# core_io4.net
KiCad netlist of a schematic drawn in EAGLE
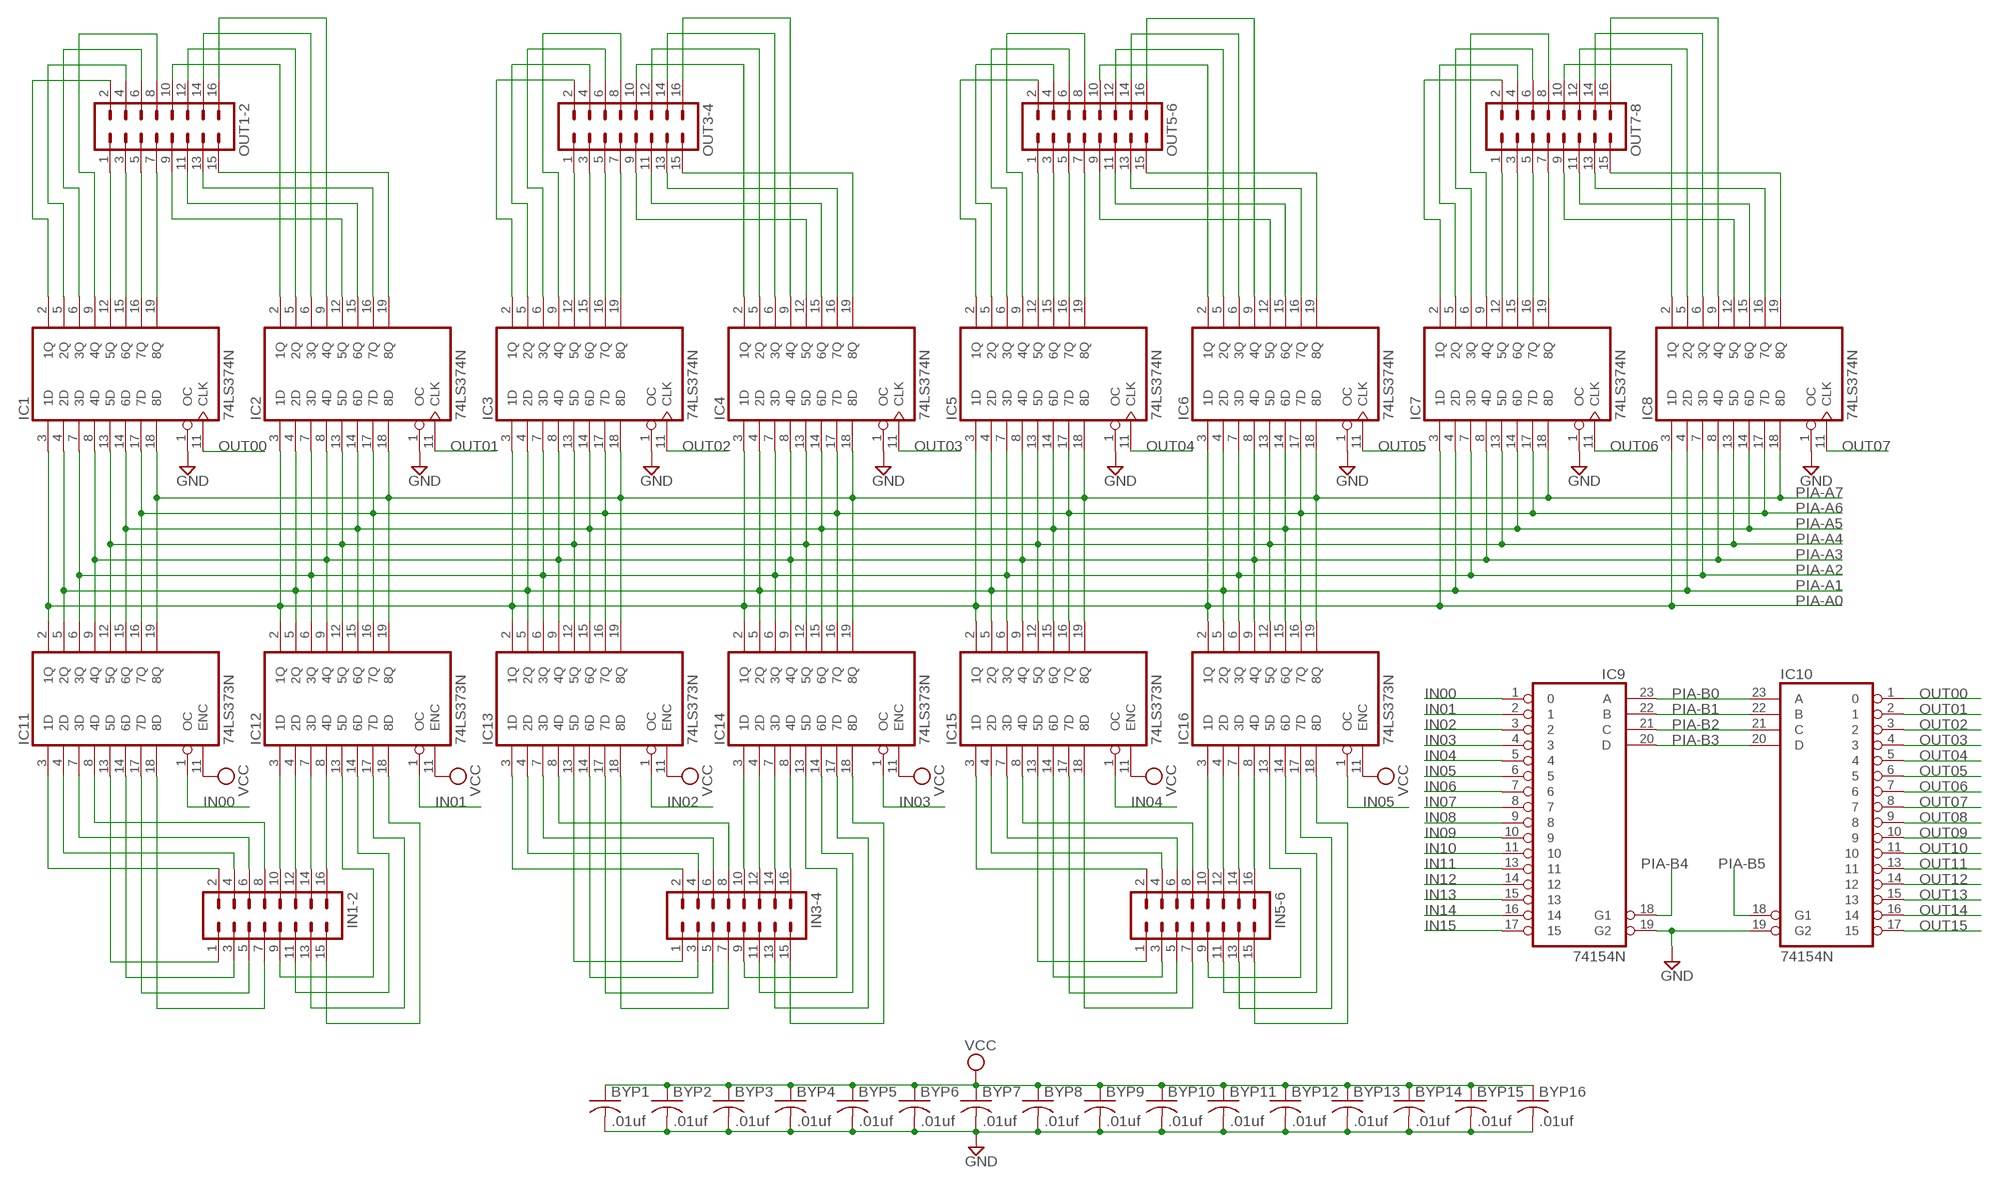
[diagram p0: schematic, sheet 1]
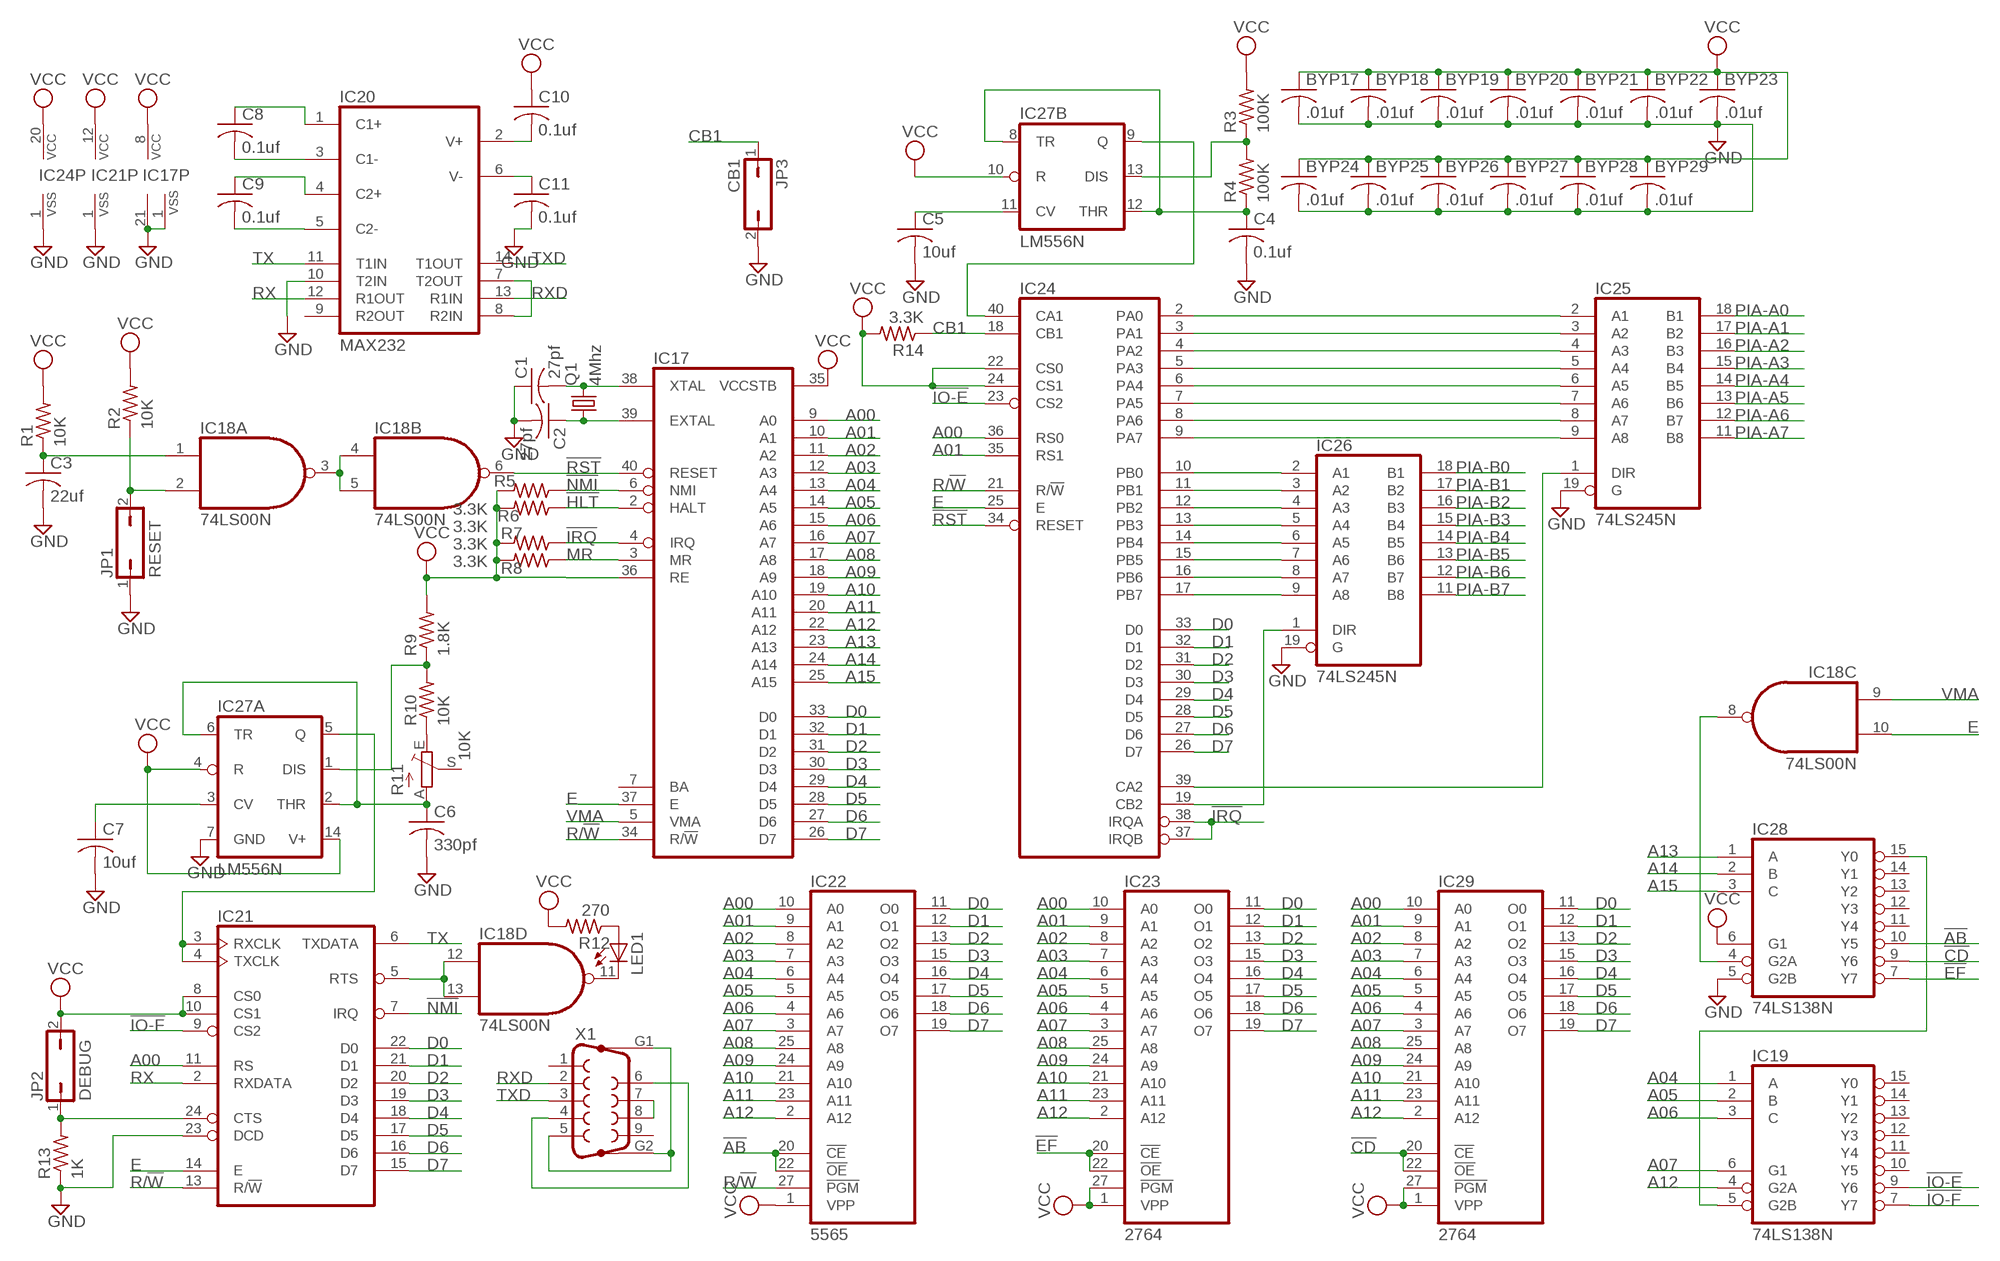
[diagram p1: schematic, sheet 2]
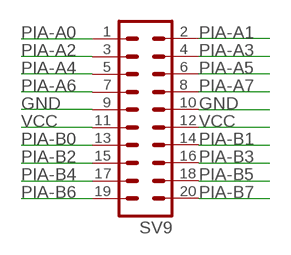
[diagram p2: schematic, sheet 3]

(export (version "E")
  (design (tool "Eeschema 10.0.6"))
  (components
    (comp (ref "BYP17")
      (value ".01uf")
      (footprint "eagle-import:C050-025X075")
      (libsource (lib "eagle-import") (part "C-US050-025X075"))
    )
    (comp (ref "BYP18")
      (value ".01uf")
      (footprint "eagle-import:C050-025X075")
      (libsource (lib "eagle-import") (part "C-US050-025X075"))
    )
    (comp (ref "BYP19")
      (value ".01uf")
      (footprint "eagle-import:C050-025X075")
      (libsource (lib "eagle-import") (part "C-US050-025X075"))
    )
    (comp (ref "BYP20")
      (value ".01uf")
      (footprint "eagle-import:C050-025X075")
      (libsource (lib "eagle-import") (part "C-US050-025X075"))
    )
    (comp (ref "BYP21")
      (value ".01uf")
      (footprint "eagle-import:C050-025X075")
      (libsource (lib "eagle-import") (part "C-US050-025X075"))
    )
    (comp (ref "BYP22")
      (value ".01uf")
      (footprint "eagle-import:C050-025X075")
      (libsource (lib "eagle-import") (part "C-US050-025X075"))
    )
    (comp (ref "BYP23")
      (value ".01uf")
      (footprint "eagle-import:C050-025X075")
      (libsource (lib "eagle-import") (part "C-US050-025X075"))
    )
    (comp (ref "BYP24")
      (value ".01uf")
      (footprint "eagle-import:C050-025X075")
      (libsource (lib "eagle-import") (part "C-US050-025X075"))
    )
    (comp (ref "BYP25")
      (value ".01uf")
      (footprint "eagle-import:C050-025X075")
      (libsource (lib "eagle-import") (part "C-US050-025X075"))
    )
    (comp (ref "BYP26")
      (value ".01uf")
      (footprint "eagle-import:C050-025X075")
      (libsource (lib "eagle-import") (part "C-US050-025X075"))
    )
    (comp (ref "BYP27")
      (value ".01uf")
      (footprint "eagle-import:C050-025X075")
      (libsource (lib "eagle-import") (part "C-US050-025X075"))
    )
    (comp (ref "BYP28")
      (value ".01uf")
      (footprint "eagle-import:C050-025X075")
      (libsource (lib "eagle-import") (part "C-US050-025X075"))
    )
    (comp (ref "BYP29")
      (value ".01uf")
      (footprint "eagle-import:C050-025X075")
      (libsource (lib "eagle-import") (part "C-US050-025X075"))
    )
    (comp (ref "C1")
      (value "27pf")
      (footprint "eagle-import:C050-025X075")
      (libsource (lib "eagle-import") (part "C-US050-025X075"))
    )
    (comp (ref "C2")
      (value "27pf")
      (footprint "eagle-import:C050-025X075")
      (libsource (lib "eagle-import") (part "C-US050-025X075"))
    )
    (comp (ref "C3")
      (value "22uf")
      (footprint "eagle-import:C102-043X133")
      (libsource (lib "eagle-import") (part "C-US102-043X133"))
    )
    (comp (ref "C4")
      (value "0.1uf")
      (footprint "eagle-import:C050-025X075")
      (libsource (lib "eagle-import") (part "C-US050-025X075"))
    )
    (comp (ref "C5")
      (value "10uf")
      (footprint "eagle-import:C050-025X075")
      (libsource (lib "eagle-import") (part "C-US050-025X075"))
    )
    (comp (ref "C6")
      (value "330pf")
      (footprint "eagle-import:C050-025X075")
      (libsource (lib "eagle-import") (part "C-US050-025X075"))
    )
    (comp (ref "C7")
      (value "10uf")
      (footprint "eagle-import:C050-025X075")
      (libsource (lib "eagle-import") (part "C-US050-025X075"))
    )
    (comp (ref "C8")
      (value "0.1uf")
      (footprint "eagle-import:C050-025X075")
      (libsource (lib "eagle-import") (part "C-US050-025X075"))
    )
    (comp (ref "C9")
      (value "0.1uf")
      (footprint "eagle-import:C050-025X075")
      (libsource (lib "eagle-import") (part "C-US050-025X075"))
    )
    (comp (ref "C10")
      (value "0.1uf")
      (footprint "eagle-import:C050-025X075")
      (libsource (lib "eagle-import") (part "C-US050-025X075"))
    )
    (comp (ref "C11")
      (value "0.1uf")
      (footprint "eagle-import:C050-025X075")
      (libsource (lib "eagle-import") (part "C-US050-025X075"))
    )
    (comp (ref "IC17")
      (value "6802")
      (footprint "eagle-import:DIL40")
      (libsource (lib "eagle-import") (part "6802"))
    )
    (comp (ref "IC18")
      (value "74LS00N")
      (footprint "eagle-import:DIL14")
      (libsource (lib "eagle-import") (part "7400NLS"))
    )
    (comp (ref "IC19")
      (value "74LS138N")
      (footprint "eagle-import:DIL16")
      (libsource (lib "eagle-import") (part "74138NLS"))
    )
    (comp (ref "IC20")
      (value "MAX232")
      (footprint "eagle-import:DIL16")
      (fields (field (name "MF") "MAXIM") (field (name "MPN") "MAX232ACPE+"))
      (libsource (lib "eagle-import") (part "MAX232"))
    )
    (comp (ref "IC21")
      (value "6850")
      (footprint "eagle-import:DIL24")
      (fields (field (name "MF") "NTE ELECTRONICS") (field (name "MPN") "NTE6850"))
      (libsource (lib "eagle-import") (part "6850"))
    )
    (comp (ref "IC22")
      (value "5565")
      (footprint "eagle-import:DIL28")
      (libsource (lib "eagle-import") (part "2764"))
    )
    (comp (ref "IC23")
      (value "2764")
      (footprint "eagle-import:DIL28")
      (libsource (lib "eagle-import") (part "2764"))
    )
    (comp (ref "IC24")
      (value "6821")
      (footprint "eagle-import:DIL40")
      (fields (field (name "MF") "NTE ELECTRONICS") (field (name "MPN") "NTE6821"))
      (libsource (lib "eagle-import") (part "6821"))
    )
    (comp (ref "IC25")
      (value "74LS245N")
      (footprint "eagle-import:DIL20")
      (libsource (lib "eagle-import") (part "74245NLS"))
    )
    (comp (ref "IC26")
      (value "74LS245N")
      (footprint "eagle-import:DIL20")
      (libsource (lib "eagle-import") (part "74245NLS"))
    )
    (comp (ref "IC27")
      (value "LM556N")
      (footprint "eagle-import:DIL14")
      (libsource (lib "eagle-import") (part "556NLM"))
    )
    (comp (ref "IC28")
      (value "74LS138N")
      (footprint "eagle-import:DIL16")
      (libsource (lib "eagle-import") (part "74138NLS"))
    )
    (comp (ref "IC29")
      (value "2764")
      (footprint "eagle-import:DIL28")
      (libsource (lib "eagle-import") (part "2764"))
    )
    (comp (ref "JP1")
      (value "RESET")
      (footprint "eagle-import:JP1")
      (libsource (lib "eagle-import") (part "JP1Q"))
    )
    (comp (ref "JP2")
      (value "DEBUG")
      (footprint "eagle-import:JP1")
      (libsource (lib "eagle-import") (part "JP1Q"))
    )
    (comp (ref "JP3")
      (value "CB1")
      (footprint "eagle-import:JP1")
      (libsource (lib "eagle-import") (part "JP1Q"))
    )
    (comp (ref "LED1")
      (value "LED3MM")
      (footprint "eagle-import:LED3MM")
      (libsource (lib "eagle-import") (part "LED3MM"))
    )
    (comp (ref "Q1")
      (value "4Mhz")
      (footprint "eagle-import:HC18U-V")
      (libsource (lib "eagle-import") (part "CRYSTALHC18U-V"))
    )
    (comp (ref "R1")
      (value "10K")
      (footprint "eagle-import:0207_7")
      (libsource (lib "eagle-import") (part "R-US_0207/7"))
    )
    (comp (ref "R2")
      (value "10K")
      (footprint "eagle-import:0207_7")
      (libsource (lib "eagle-import") (part "R-US_0207/7"))
    )
    (comp (ref "R3")
      (value "100K")
      (footprint "eagle-import:0207_7")
      (libsource (lib "eagle-import") (part "R-US_0207/7"))
    )
    (comp (ref "R4")
      (value "100K")
      (footprint "eagle-import:0207_7")
      (libsource (lib "eagle-import") (part "R-US_0207/7"))
    )
    (comp (ref "R5")
      (value "3.3K")
      (footprint "eagle-import:0207_7")
      (libsource (lib "eagle-import") (part "R-US_0207/7"))
    )
    (comp (ref "R6")
      (value "3.3K")
      (footprint "eagle-import:0207_7")
      (libsource (lib "eagle-import") (part "R-US_0207/7"))
    )
    (comp (ref "R7")
      (value "3.3K")
      (footprint "eagle-import:0207_7")
      (libsource (lib "eagle-import") (part "R-US_0207/7"))
    )
    (comp (ref "R8")
      (value "3.3K")
      (footprint "eagle-import:0207_7")
      (libsource (lib "eagle-import") (part "R-US_0207/7"))
    )
    (comp (ref "R9")
      (value "1.8K")
      (footprint "eagle-import:0207_7")
      (libsource (lib "eagle-import") (part "R-US_0207/7"))
    )
    (comp (ref "R10")
      (value "10K")
      (footprint "eagle-import:0207_7")
      (libsource (lib "eagle-import") (part "R-US_0207/7"))
    )
    (comp (ref "R11")
      (value "10K")
      (footprint "eagle-import:SP19L")
      (libsource (lib "eagle-import") (part "TRIM_EU-B90P"))
    )
    (comp (ref "R12")
      (value "270")
      (footprint "eagle-import:0207_7")
      (libsource (lib "eagle-import") (part "R-US_0207/7"))
    )
    (comp (ref "R13")
      (value "1K")
      (footprint "eagle-import:0207_7")
      (libsource (lib "eagle-import") (part "R-US_0207/7"))
    )
    (comp (ref "R14")
      (value "3.3K")
      (footprint "eagle-import:0207_7")
      (libsource (lib "eagle-import") (part "R-US_0207/7"))
    )
    (comp (ref "X1")
      (value "F09HP")
      (footprint "eagle-import:F09HP")
      (libsource (lib "eagle-import") (part "F09HP"))
    )
    (comp (ref "SV9")
      (value "MA10-2")
      (footprint "eagle-import:MA10-2")
      (libsource (lib "eagle-import") (part "MA10-2"))
    )
    (comp (ref "BYP1")
      (value ".01uf")
      (footprint "eagle-import:C050-025X075")
      (libsource (lib "eagle-import") (part "C-US050-025X075"))
    )
    (comp (ref "BYP2")
      (value ".01uf")
      (footprint "eagle-import:C050-025X075")
      (libsource (lib "eagle-import") (part "C-US050-025X075"))
    )
    (comp (ref "BYP3")
      (value ".01uf")
      (footprint "eagle-import:C050-025X075")
      (libsource (lib "eagle-import") (part "C-US050-025X075"))
    )
    (comp (ref "BYP4")
      (value ".01uf")
      (footprint "eagle-import:C050-025X075")
      (libsource (lib "eagle-import") (part "C-US050-025X075"))
    )
    (comp (ref "BYP5")
      (value ".01uf")
      (footprint "eagle-import:C050-025X075")
      (libsource (lib "eagle-import") (part "C-US050-025X075"))
    )
    (comp (ref "BYP6")
      (value ".01uf")
      (footprint "eagle-import:C050-025X075")
      (libsource (lib "eagle-import") (part "C-US050-025X075"))
    )
    (comp (ref "BYP7")
      (value ".01uf")
      (footprint "eagle-import:C050-025X075")
      (libsource (lib "eagle-import") (part "C-US050-025X075"))
    )
    (comp (ref "BYP8")
      (value ".01uf")
      (footprint "eagle-import:C050-025X075")
      (libsource (lib "eagle-import") (part "C-US050-025X075"))
    )
    (comp (ref "BYP9")
      (value ".01uf")
      (footprint "eagle-import:C050-025X075")
      (libsource (lib "eagle-import") (part "C-US050-025X075"))
    )
    (comp (ref "BYP10")
      (value ".01uf")
      (footprint "eagle-import:C050-025X075")
      (libsource (lib "eagle-import") (part "C-US050-025X075"))
    )
    (comp (ref "BYP11")
      (value ".01uf")
      (footprint "eagle-import:C050-025X075")
      (libsource (lib "eagle-import") (part "C-US050-025X075"))
    )
    (comp (ref "BYP12")
      (value ".01uf")
      (footprint "eagle-import:C050-025X075")
      (libsource (lib "eagle-import") (part "C-US050-025X075"))
    )
    (comp (ref "BYP13")
      (value ".01uf")
      (footprint "eagle-import:C050-025X075")
      (libsource (lib "eagle-import") (part "C-US050-025X075"))
    )
    (comp (ref "BYP14")
      (value ".01uf")
      (footprint "eagle-import:C050-025X075")
      (libsource (lib "eagle-import") (part "C-US050-025X075"))
    )
    (comp (ref "BYP15")
      (value ".01uf")
      (footprint "eagle-import:C050-025X075")
      (libsource (lib "eagle-import") (part "C-US050-025X075"))
    )
    (comp (ref "BYP16")
      (value ".01uf")
      (footprint "eagle-import:C050-025X075")
      (libsource (lib "eagle-import") (part "C-US050-025X075"))
    )
    (comp (ref "IC1")
      (value "74LS374N")
      (footprint "eagle-import:DIL20")
      (libsource (lib "eagle-import") (part "74374NLS"))
    )
    (comp (ref "IC2")
      (value "74LS374N")
      (footprint "eagle-import:DIL20")
      (libsource (lib "eagle-import") (part "74374NLS"))
    )
    (comp (ref "IC3")
      (value "74LS374N")
      (footprint "eagle-import:DIL20")
      (libsource (lib "eagle-import") (part "74374NLS"))
    )
    (comp (ref "IC4")
      (value "74LS374N")
      (footprint "eagle-import:DIL20")
      (libsource (lib "eagle-import") (part "74374NLS"))
    )
    (comp (ref "IC5")
      (value "74LS374N")
      (footprint "eagle-import:DIL20")
      (libsource (lib "eagle-import") (part "74374NLS"))
    )
    (comp (ref "IC6")
      (value "74LS374N")
      (footprint "eagle-import:DIL20")
      (libsource (lib "eagle-import") (part "74374NLS"))
    )
    (comp (ref "IC7")
      (value "74LS374N")
      (footprint "eagle-import:DIL20")
      (libsource (lib "eagle-import") (part "74374NLS"))
    )
    (comp (ref "IC8")
      (value "74LS374N")
      (footprint "eagle-import:DIL20")
      (libsource (lib "eagle-import") (part "74374NLS"))
    )
    (comp (ref "IC9")
      (value "74154N")
      (footprint "eagle-import:DIL24-6")
      (libsource (lib "eagle-import") (part "74154N"))
    )
    (comp (ref "IC10")
      (value "74154N")
      (footprint "eagle-import:DIL24-6")
      (libsource (lib "eagle-import") (part "74154N"))
    )
    (comp (ref "IC11")
      (value "74LS373N")
      (footprint "eagle-import:DIL20")
      (libsource (lib "eagle-import") (part "74373NLS"))
    )
    (comp (ref "IC12")
      (value "74LS373N")
      (footprint "eagle-import:DIL20")
      (libsource (lib "eagle-import") (part "74373NLS"))
    )
    (comp (ref "IC13")
      (value "74LS373N")
      (footprint "eagle-import:DIL20")
      (libsource (lib "eagle-import") (part "74373NLS"))
    )
    (comp (ref "IC14")
      (value "74LS373N")
      (footprint "eagle-import:DIL20")
      (libsource (lib "eagle-import") (part "74373NLS"))
    )
    (comp (ref "IC15")
      (value "74LS373N")
      (footprint "eagle-import:DIL20")
      (libsource (lib "eagle-import") (part "74373NLS"))
    )
    (comp (ref "IC16")
      (value "74LS373N")
      (footprint "eagle-import:DIL20")
      (libsource (lib "eagle-import") (part "74373NLS"))
    )
    (comp (ref "IN1-2")
      (value "MA08-2")
      (footprint "eagle-import:MA08-2")
      (libsource (lib "eagle-import") (part "MA08-2"))
    )
    (comp (ref "IN3-4")
      (value "MA08-2")
      (footprint "eagle-import:MA08-2")
      (libsource (lib "eagle-import") (part "MA08-2"))
    )
    (comp (ref "IN5-6")
      (value "MA08-2")
      (footprint "eagle-import:MA08-2")
      (libsource (lib "eagle-import") (part "MA08-2"))
    )
    (comp (ref "OUT1-2")
      (value "MA08-2")
      (footprint "eagle-import:MA08-2")
      (libsource (lib "eagle-import") (part "MA08-2"))
    )
    (comp (ref "OUT3-4")
      (value "MA08-2")
      (footprint "eagle-import:MA08-2")
      (libsource (lib "eagle-import") (part "MA08-2"))
    )
    (comp (ref "OUT5-6")
      (value "MA08-2")
      (footprint "eagle-import:MA08-2")
      (libsource (lib "eagle-import") (part "MA08-2"))
    )
    (comp (ref "OUT7-8")
      (value "MA08-2")
      (footprint "eagle-import:MA08-2")
      (libsource (lib "eagle-import") (part "MA08-2"))
    )
  )
  (nets
    (net (code "1") (name "A00") (class "Default")
      (node (ref "IC17") (pin "9") (pinfunction "A0_9") (pintype "output"))
      (node (ref "IC21") (pin "11") (pinfunction "RS_11") (pintype "input"))
      (node (ref "IC22") (pin "10") (pinfunction "A0_10") (pintype "input"))
      (node (ref "IC23") (pin "10") (pinfunction "A0_10") (pintype "input"))
      (node (ref "IC24") (pin "36") (pinfunction "RS0_36") (pintype "input"))
      (node (ref "IC29") (pin "10") (pinfunction "A0_10") (pintype "input"))
    )
    (net (code "2") (name "A01") (class "Default")
      (node (ref "IC17") (pin "10") (pinfunction "A1_10") (pintype "output"))
      (node (ref "IC22") (pin "9") (pinfunction "A1_9") (pintype "input"))
      (node (ref "IC23") (pin "9") (pinfunction "A1_9") (pintype "input"))
      (node (ref "IC24") (pin "35") (pinfunction "RS1_35") (pintype "input"))
      (node (ref "IC29") (pin "9") (pinfunction "A1_9") (pintype "input"))
    )
    (net (code "3") (name "A02") (class "Default")
      (node (ref "IC17") (pin "11") (pinfunction "A2_11") (pintype "output"))
      (node (ref "IC22") (pin "8") (pinfunction "A2_8") (pintype "input"))
      (node (ref "IC23") (pin "8") (pinfunction "A2_8") (pintype "input"))
      (node (ref "IC29") (pin "8") (pinfunction "A2_8") (pintype "input"))
    )
    (net (code "4") (name "A03") (class "Default")
      (node (ref "IC17") (pin "12") (pinfunction "A3_12") (pintype "output"))
      (node (ref "IC22") (pin "7") (pinfunction "A3_7") (pintype "input"))
      (node (ref "IC23") (pin "7") (pinfunction "A3_7") (pintype "input"))
      (node (ref "IC29") (pin "7") (pinfunction "A3_7") (pintype "input"))
    )
    (net (code "5") (name "A04") (class "Default")
      (node (ref "IC17") (pin "13") (pinfunction "A4_13") (pintype "output"))
      (node (ref "IC19") (pin "1") (pinfunction "A_1") (pintype "input"))
      (node (ref "IC22") (pin "6") (pinfunction "A4_6") (pintype "input"))
      (node (ref "IC23") (pin "6") (pinfunction "A4_6") (pintype "input"))
      (node (ref "IC29") (pin "6") (pinfunction "A4_6") (pintype "input"))
    )
    (net (code "6") (name "A05") (class "Default")
      (node (ref "IC17") (pin "14") (pinfunction "A5_14") (pintype "output"))
      (node (ref "IC19") (pin "2") (pinfunction "B_2") (pintype "input"))
      (node (ref "IC22") (pin "5") (pinfunction "A5_5") (pintype "input"))
      (node (ref "IC23") (pin "5") (pinfunction "A5_5") (pintype "input"))
      (node (ref "IC29") (pin "5") (pinfunction "A5_5") (pintype "input"))
    )
    (net (code "7") (name "A06") (class "Default")
      (node (ref "IC17") (pin "15") (pinfunction "A6_15") (pintype "output"))
      (node (ref "IC19") (pin "3") (pinfunction "C_3") (pintype "input"))
      (node (ref "IC22") (pin "4") (pinfunction "A6_4") (pintype "input"))
      (node (ref "IC23") (pin "4") (pinfunction "A6_4") (pintype "input"))
      (node (ref "IC29") (pin "4") (pinfunction "A6_4") (pintype "input"))
    )
    (net (code "8") (name "A07") (class "Default")
      (node (ref "IC17") (pin "16") (pinfunction "A7_16") (pintype "output"))
      (node (ref "IC19") (pin "6") (pinfunction "G1_6") (pintype "input"))
      (node (ref "IC22") (pin "3") (pinfunction "A7_3") (pintype "input"))
      (node (ref "IC23") (pin "3") (pinfunction "A7_3") (pintype "input"))
      (node (ref "IC29") (pin "3") (pinfunction "A7_3") (pintype "input"))
    )
    (net (code "9") (name "A08") (class "Default")
      (node (ref "IC17") (pin "17") (pinfunction "A8_17") (pintype "output"))
      (node (ref "IC22") (pin "25") (pinfunction "A8_25") (pintype "input"))
      (node (ref "IC23") (pin "25") (pinfunction "A8_25") (pintype "input"))
      (node (ref "IC29") (pin "25") (pinfunction "A8_25") (pintype "input"))
    )
    (net (code "10") (name "A09") (class "Default")
      (node (ref "IC17") (pin "18") (pinfunction "A9_18") (pintype "output"))
      (node (ref "IC22") (pin "24") (pinfunction "A9_24") (pintype "input"))
      (node (ref "IC23") (pin "24") (pinfunction "A9_24") (pintype "input"))
      (node (ref "IC29") (pin "24") (pinfunction "A9_24") (pintype "input"))
    )
    (net (code "11") (name "A10") (class "Default")
      (node (ref "IC17") (pin "19") (pinfunction "A10_19") (pintype "output"))
      (node (ref "IC22") (pin "21") (pinfunction "A10_21") (pintype "input"))
      (node (ref "IC23") (pin "21") (pinfunction "A10_21") (pintype "input"))
      (node (ref "IC29") (pin "21") (pinfunction "A10_21") (pintype "input"))
    )
    (net (code "12") (name "A11") (class "Default")
      (node (ref "IC17") (pin "20") (pinfunction "A11_20") (pintype "output"))
      (node (ref "IC22") (pin "23") (pinfunction "A11_23") (pintype "input"))
      (node (ref "IC23") (pin "23") (pinfunction "A11_23") (pintype "input"))
      (node (ref "IC29") (pin "23") (pinfunction "A11_23") (pintype "input"))
    )
    (net (code "13") (name "A12") (class "Default")
      (node (ref "IC17") (pin "22") (pinfunction "A12_22") (pintype "output"))
      (node (ref "IC19") (pin "4") (pinfunction "G2A_4") (pintype "input"))
      (node (ref "IC22") (pin "2") (pinfunction "A12_2") (pintype "input"))
      (node (ref "IC23") (pin "2") (pinfunction "A12_2") (pintype "input"))
      (node (ref "IC29") (pin "2") (pinfunction "A12_2") (pintype "input"))
    )
    (net (code "14") (name "A13") (class "Default")
      (node (ref "IC17") (pin "23") (pinfunction "A13_23") (pintype "output"))
      (node (ref "IC28") (pin "1") (pinfunction "A_1") (pintype "input"))
    )
    (net (code "15") (name "A14") (class "Default")
      (node (ref "IC17") (pin "24") (pinfunction "A14_24") (pintype "output"))
      (node (ref "IC28") (pin "2") (pinfunction "B_2") (pintype "input"))
    )
    (net (code "16") (name "A15") (class "Default")
      (node (ref "IC17") (pin "25") (pinfunction "A15_25") (pintype "output"))
      (node (ref "IC28") (pin "3") (pinfunction "C_3") (pintype "input"))
    )
    (net (code "17") (name "CB1") (class "Default")
      (node (ref "IC24") (pin "18") (pinfunction "CB1_18") (pintype "input"))
      (node (ref "JP3") (pin "1") (pinfunction "1_1") (pintype "passive"))
      (node (ref "R14") (pin "1") (pinfunction "1_1") (pintype "passive"))
    )
    (net (code "18") (name "D0") (class "Default")
      (node (ref "IC17") (pin "33") (pinfunction "D0_33") (pintype "bidirectional"))
      (node (ref "IC21") (pin "22") (pinfunction "D0_22") (pintype "bidirectional"))
      (node (ref "IC22") (pin "11") (pinfunction "O0_11") (pintype "tri_state"))
      (node (ref "IC23") (pin "11") (pinfunction "O0_11") (pintype "tri_state"))
      (node (ref "IC24") (pin "33") (pinfunction "D0_33") (pintype "bidirectional"))
      (node (ref "IC29") (pin "11") (pinfunction "O0_11") (pintype "tri_state"))
    )
    (net (code "19") (name "D1") (class "Default")
      (node (ref "IC17") (pin "32") (pinfunction "D1_32") (pintype "bidirectional"))
      (node (ref "IC21") (pin "21") (pinfunction "D1_21") (pintype "bidirectional"))
      (node (ref "IC22") (pin "12") (pinfunction "O1_12") (pintype "tri_state"))
      (node (ref "IC23") (pin "12") (pinfunction "O1_12") (pintype "tri_state"))
      (node (ref "IC24") (pin "32") (pinfunction "D1_32") (pintype "bidirectional"))
      (node (ref "IC29") (pin "12") (pinfunction "O1_12") (pintype "tri_state"))
    )
    (net (code "20") (name "D2") (class "Default")
      (node (ref "IC17") (pin "31") (pinfunction "D2_31") (pintype "bidirectional"))
      (node (ref "IC21") (pin "20") (pinfunction "D2_20") (pintype "bidirectional"))
      (node (ref "IC22") (pin "13") (pinfunction "O2_13") (pintype "tri_state"))
      (node (ref "IC23") (pin "13") (pinfunction "O2_13") (pintype "tri_state"))
      (node (ref "IC24") (pin "31") (pinfunction "D2_31") (pintype "bidirectional"))
      (node (ref "IC29") (pin "13") (pinfunction "O2_13") (pintype "tri_state"))
    )
    (net (code "21") (name "D3") (class "Default")
      (node (ref "IC17") (pin "30") (pinfunction "D3_30") (pintype "bidirectional"))
      (node (ref "IC21") (pin "19") (pinfunction "D3_19") (pintype "bidirectional"))
      (node (ref "IC22") (pin "15") (pinfunction "O3_15") (pintype "tri_state"))
      (node (ref "IC23") (pin "15") (pinfunction "O3_15") (pintype "tri_state"))
      (node (ref "IC24") (pin "30") (pinfunction "D3_30") (pintype "bidirectional"))
      (node (ref "IC29") (pin "15") (pinfunction "O3_15") (pintype "tri_state"))
    )
    (net (code "22") (name "D4") (class "Default")
      (node (ref "IC17") (pin "29") (pinfunction "D4_29") (pintype "bidirectional"))
      (node (ref "IC21") (pin "18") (pinfunction "D4_18") (pintype "bidirectional"))
      (node (ref "IC22") (pin "16") (pinfunction "O4_16") (pintype "tri_state"))
      (node (ref "IC23") (pin "16") (pinfunction "O4_16") (pintype "tri_state"))
      (node (ref "IC24") (pin "29") (pinfunction "D4_29") (pintype "bidirectional"))
      (node (ref "IC29") (pin "16") (pinfunction "O4_16") (pintype "tri_state"))
    )
    (net (code "23") (name "D5") (class "Default")
      (node (ref "IC17") (pin "28") (pinfunction "D5_28") (pintype "bidirectional"))
      (node (ref "IC21") (pin "17") (pinfunction "D5_17") (pintype "bidirectional"))
      (node (ref "IC22") (pin "17") (pinfunction "O5_17") (pintype "tri_state"))
      (node (ref "IC23") (pin "17") (pinfunction "O5_17") (pintype "tri_state"))
      (node (ref "IC24") (pin "28") (pinfunction "D5_28") (pintype "bidirectional"))
      (node (ref "IC29") (pin "17") (pinfunction "O5_17") (pintype "tri_state"))
    )
    (net (code "24") (name "D6") (class "Default")
      (node (ref "IC17") (pin "27") (pinfunction "D6_27") (pintype "bidirectional"))
      (node (ref "IC21") (pin "16") (pinfunction "D6_16") (pintype "bidirectional"))
      (node (ref "IC22") (pin "18") (pinfunction "O6_18") (pintype "tri_state"))
      (node (ref "IC23") (pin "18") (pinfunction "O6_18") (pintype "tri_state"))
      (node (ref "IC24") (pin "27") (pinfunction "D6_27") (pintype "bidirectional"))
      (node (ref "IC29") (pin "18") (pinfunction "O6_18") (pintype "tri_state"))
    )
    (net (code "25") (name "D7") (class "Default")
      (node (ref "IC17") (pin "26") (pinfunction "D7_26") (pintype "bidirectional"))
      (node (ref "IC21") (pin "15") (pinfunction "D7_15") (pintype "bidirectional"))
      (node (ref "IC22") (pin "19") (pinfunction "O7_19") (pintype "tri_state"))
      (node (ref "IC23") (pin "19") (pinfunction "O7_19") (pintype "tri_state"))
      (node (ref "IC24") (pin "26") (pinfunction "D7_26") (pintype "bidirectional"))
      (node (ref "IC29") (pin "19") (pinfunction "O7_19") (pintype "tri_state"))
    )
    (net (code "26") (name "E") (class "Default")
      (node (ref "IC17") (pin "37") (pinfunction "E_37") (pintype "output"))
      (node (ref "IC18") (pin "10") (pinfunction "I1_10") (pintype "input"))
      (node (ref "IC21") (pin "14") (pinfunction "E_14") (pintype "input"))
      (node (ref "IC24") (pin "25") (pinfunction "E_25") (pintype "input"))
    )
    (net (code "27") (name "GND") (class "Default")
      (node (ref "BYP1") (pin "2") (pinfunction "2_2") (pintype "passive"))
      (node (ref "BYP10") (pin "2") (pinfunction "2_2") (pintype "passive"))
      (node (ref "BYP11") (pin "2") (pinfunction "2_2") (pintype "passive"))
      (node (ref "BYP12") (pin "2") (pinfunction "2_2") (pintype "passive"))
      (node (ref "BYP13") (pin "2") (pinfunction "2_2") (pintype "passive"))
      (node (ref "BYP14") (pin "2") (pinfunction "2_2") (pintype "passive"))
      (node (ref "BYP15") (pin "2") (pinfunction "2_2") (pintype "passive"))
      (node (ref "BYP16") (pin "2") (pinfunction "2_2") (pintype "passive"))
      (node (ref "BYP17") (pin "2") (pinfunction "2_2") (pintype "passive"))
      (node (ref "BYP18") (pin "2") (pinfunction "2_2") (pintype "passive"))
      (node (ref "BYP19") (pin "2") (pinfunction "2_2") (pintype "passive"))
      (node (ref "BYP2") (pin "2") (pinfunction "2_2") (pintype "passive"))
      (node (ref "BYP20") (pin "2") (pinfunction "2_2") (pintype "passive"))
      (node (ref "BYP21") (pin "2") (pinfunction "2_2") (pintype "passive"))
      (node (ref "BYP22") (pin "2") (pinfunction "2_2") (pintype "passive"))
      (node (ref "BYP23") (pin "2") (pinfunction "2_2") (pintype "passive"))
      (node (ref "BYP24") (pin "2") (pinfunction "2_2") (pintype "passive"))
      (node (ref "BYP25") (pin "2") (pinfunction "2_2") (pintype "passive"))
      (node (ref "BYP26") (pin "2") (pinfunction "2_2") (pintype "passive"))
      (node (ref "BYP27") (pin "2") (pinfunction "2_2") (pintype "passive"))
      (node (ref "BYP28") (pin "2") (pinfunction "2_2") (pintype "passive"))
      (node (ref "BYP29") (pin "2") (pinfunction "2_2") (pintype "passive"))
      (node (ref "BYP3") (pin "2") (pinfunction "2_2") (pintype "passive"))
      (node (ref "BYP4") (pin "2") (pinfunction "2_2") (pintype "passive"))
      (node (ref "BYP5") (pin "2") (pinfunction "2_2") (pintype "passive"))
      (node (ref "BYP6") (pin "2") (pinfunction "2_2") (pintype "passive"))
      (node (ref "BYP7") (pin "2") (pinfunction "2_2") (pintype "passive"))
      (node (ref "BYP8") (pin "2") (pinfunction "2_2") (pintype "passive"))
      (node (ref "BYP9") (pin "2") (pinfunction "2_2") (pintype "passive"))
      (node (ref "C1") (pin "1") (pinfunction "1_1") (pintype "passive"))
      (node (ref "C11") (pin "2") (pinfunction "2_2") (pintype "passive"))
      (node (ref "C2") (pin "2") (pinfunction "2_2") (pintype "passive"))
      (node (ref "C3") (pin "2") (pinfunction "2_2") (pintype "passive"))
      (node (ref "C4") (pin "2") (pinfunction "2_2") (pintype "passive"))
      (node (ref "C5") (pin "2") (pinfunction "2_2") (pintype "passive"))
      (node (ref "C6") (pin "2") (pinfunction "2_2") (pintype "passive"))
      (node (ref "C7") (pin "2") (pinfunction "2_2") (pintype "passive"))
      (node (ref "IC1") (pin "1") (pinfunction "OC_1") (pintype "input"))
      (node (ref "IC10") (pin "19") (pinfunction "G2_19") (pintype "input"))
      (node (ref "IC17") (pin "1") (pinfunction "VSS_1") (pintype "power_in"))
      (node (ref "IC17") (pin "21") (pinfunction "VSS_21") (pintype "power_in"))
      (node (ref "IC2") (pin "1") (pinfunction "OC_1") (pintype "input"))
      (node (ref "IC20") (pin "10") (pinfunction "T2IN_10") (pintype "input"))
      (node (ref "IC21") (pin "1") (pinfunction "VSS_1") (pintype "power_in"))
      (node (ref "IC21") (pin "23") (pinfunction "DCD_23") (pintype "input"))
      (node (ref "IC24") (pin "1") (pinfunction "VSS_1") (pintype "power_in"))
      (node (ref "IC25") (pin "19") (pinfunction "G_19") (pintype "input"))
      (node (ref "IC26") (pin "19") (pinfunction "G_19") (pintype "input"))
      (node (ref "IC27") (pin "7") (pinfunction "GND_7") (pintype "power_in"))
      (node (ref "IC28") (pin "5") (pinfunction "G2B_5") (pintype "input"))
      (node (ref "IC3") (pin "1") (pinfunction "OC_1") (pintype "input"))
      (node (ref "IC4") (pin "1") (pinfunction "OC_1") (pintype "input"))
      (node (ref "IC5") (pin "1") (pinfunction "OC_1") (pintype "input"))
      (node (ref "IC6") (pin "1") (pinfunction "OC_1") (pintype "input"))
      (node (ref "IC7") (pin "1") (pinfunction "OC_1") (pintype "input"))
      (node (ref "IC8") (pin "1") (pinfunction "OC_1") (pintype "input"))
      (node (ref "IC9") (pin "19") (pinfunction "G2_19") (pintype "input"))
      (node (ref "JP1") (pin "1") (pinfunction "1_1") (pintype "passive"))
      (node (ref "JP3") (pin "2") (pinfunction "2_2") (pintype "passive"))
      (node (ref "R13") (pin "1") (pinfunction "1_1") (pintype "passive"))
      (node (ref "SV9") (pin "10") (pinfunction "10_10") (pintype "passive"))
      (node (ref "SV9") (pin "9") (pinfunction "9_9") (pintype "passive"))
    )
    (net (code "28") (name "IN00") (class "Default")
      (node (ref "IC11") (pin "1") (pinfunction "OC_1") (pintype "input"))
      (node (ref "IC9") (pin "1") (pinfunction "0_1") (pintype "output"))
    )
    (net (code "29") (name "IN01") (class "Default")
      (node (ref "IC12") (pin "1") (pinfunction "OC_1") (pintype "input"))
      (node (ref "IC9") (pin "2") (pinfunction "1_2") (pintype "output"))
    )
    (net (code "30") (name "IN02") (class "Default")
      (node (ref "IC13") (pin "1") (pinfunction "OC_1") (pintype "input"))
      (node (ref "IC9") (pin "3") (pinfunction "2_3") (pintype "output"))
    )
    (net (code "31") (name "IN03") (class "Default")
      (node (ref "IC14") (pin "1") (pinfunction "OC_1") (pintype "input"))
      (node (ref "IC9") (pin "4") (pinfunction "3_4") (pintype "output"))
    )
    (net (code "32") (name "IN04") (class "Default")
      (node (ref "IC15") (pin "1") (pinfunction "OC_1") (pintype "input"))
      (node (ref "IC9") (pin "5") (pinfunction "4_5") (pintype "output"))
    )
    (net (code "33") (name "IN05") (class "Default")
      (node (ref "IC16") (pin "1") (pinfunction "OC_1") (pintype "input"))
      (node (ref "IC9") (pin "6") (pinfunction "5_6") (pintype "output"))
    )
    (net (code "34") (name "IN06") (class "Default")
      (node (ref "IC9") (pin "7") (pinfunction "6_7") (pintype "output"))
    )
    (net (code "35") (name "IN07") (class "Default")
      (node (ref "IC9") (pin "8") (pinfunction "7_8") (pintype "output"))
    )
    (net (code "36") (name "IN08") (class "Default")
      (node (ref "IC9") (pin "9") (pinfunction "8_9") (pintype "output"))
    )
    (net (code "37") (name "IN09") (class "Default")
      (node (ref "IC9") (pin "10") (pinfunction "9_10") (pintype "output"))
    )
    (net (code "38") (name "IN10") (class "Default")
      (node (ref "IC9") (pin "11") (pinfunction "10_11") (pintype "output"))
    )
    (net (code "39") (name "IN11") (class "Default")
      (node (ref "IC9") (pin "13") (pinfunction "11_13") (pintype "output"))
    )
    (net (code "40") (name "IN12") (class "Default")
      (node (ref "IC9") (pin "14") (pinfunction "12_14") (pintype "output"))
    )
    (net (code "41") (name "IN13") (class "Default")
      (node (ref "IC9") (pin "15") (pinfunction "13_15") (pintype "output"))
    )
    (net (code "42") (name "IN14") (class "Default")
      (node (ref "IC9") (pin "16") (pinfunction "14_16") (pintype "output"))
    )
    (net (code "43") (name "IN15") (class "Default")
      (node (ref "IC9") (pin "17") (pinfunction "15_17") (pintype "output"))
    )
    (net (code "44") (name "MR") (class "Default")
      (node (ref "IC17") (pin "3") (pinfunction "MR_3") (pintype "input"))
      (node (ref "R8") (pin "1") (pinfunction "1_1") (pintype "passive"))
    )
    (net (code "45") (name "Net-(IC1A-1Q)") (class "Default")
      (node (ref "IC1") (pin "2") (pinfunction "1Q_2") (pintype "tri_state"))
      (node (ref "OUT1-2") (pin "2") (pinfunction "2_2") (pintype "passive"))
    )
    (net (code "46") (name "Net-(IC1A-2Q)") (class "Default")
      (node (ref "IC1") (pin "5") (pinfunction "2Q_5") (pintype "tri_state"))
      (node (ref "OUT1-2") (pin "4") (pinfunction "4_4") (pintype "passive"))
    )
    (net (code "47") (name "Net-(IC1A-3Q)") (class "Default")
      (node (ref "IC1") (pin "6") (pinfunction "3Q_6") (pintype "tri_state"))
      (node (ref "OUT1-2") (pin "6") (pinfunction "6_6") (pintype "passive"))
    )
    (net (code "48") (name "Net-(IC1A-4Q)") (class "Default")
      (node (ref "IC1") (pin "9") (pinfunction "4Q_9") (pintype "tri_state"))
      (node (ref "OUT1-2") (pin "8") (pinfunction "8_8") (pintype "passive"))
    )
    (net (code "49") (name "Net-(IC1A-5Q)") (class "Default")
      (node (ref "IC1") (pin "12") (pinfunction "5Q_12") (pintype "tri_state"))
      (node (ref "OUT1-2") (pin "1") (pinfunction "1_1") (pintype "passive"))
    )
    (net (code "50") (name "Net-(IC1A-6Q)") (class "Default")
      (node (ref "IC1") (pin "15") (pinfunction "6Q_15") (pintype "tri_state"))
      (node (ref "OUT1-2") (pin "3") (pinfunction "3_3") (pintype "passive"))
    )
    (net (code "51") (name "Net-(IC1A-7Q)") (class "Default")
      (node (ref "IC1") (pin "16") (pinfunction "7Q_16") (pintype "tri_state"))
      (node (ref "OUT1-2") (pin "5") (pinfunction "5_5") (pintype "passive"))
    )
    (net (code "52") (name "Net-(IC1A-8Q)") (class "Default")
      (node (ref "IC1") (pin "19") (pinfunction "8Q_19") (pintype "tri_state"))
      (node (ref "OUT1-2") (pin "7") (pinfunction "7_7") (pintype "passive"))
    )
    (net (code "53") (name "Net-(IC2A-1Q)") (class "Default")
      (node (ref "IC2") (pin "2") (pinfunction "1Q_2") (pintype "tri_state"))
      (node (ref "OUT1-2") (pin "10") (pinfunction "10_10") (pintype "passive"))
    )
    (net (code "54") (name "Net-(IC2A-2Q)") (class "Default")
      (node (ref "IC2") (pin "5") (pinfunction "2Q_5") (pintype "tri_state"))
      (node (ref "OUT1-2") (pin "12") (pinfunction "12_12") (pintype "passive"))
    )
    (net (code "55") (name "Net-(IC2A-3Q)") (class "Default")
      (node (ref "IC2") (pin "6") (pinfunction "3Q_6") (pintype "tri_state"))
      (node (ref "OUT1-2") (pin "14") (pinfunction "14_14") (pintype "passive"))
    )
    (net (code "56") (name "Net-(IC2A-4Q)") (class "Default")
      (node (ref "IC2") (pin "9") (pinfunction "4Q_9") (pintype "tri_state"))
      (node (ref "OUT1-2") (pin "16") (pinfunction "16_16") (pintype "passive"))
    )
    (net (code "57") (name "Net-(IC2A-5Q)") (class "Default")
      (node (ref "IC2") (pin "12") (pinfunction "5Q_12") (pintype "tri_state"))
      (node (ref "OUT1-2") (pin "9") (pinfunction "9_9") (pintype "passive"))
    )
    (net (code "58") (name "Net-(IC2A-6Q)") (class "Default")
      (node (ref "IC2") (pin "15") (pinfunction "6Q_15") (pintype "tri_state"))
      (node (ref "OUT1-2") (pin "11") (pinfunction "11_11") (pintype "passive"))
    )
    (net (code "59") (name "Net-(IC2A-7Q)") (class "Default")
      (node (ref "IC2") (pin "16") (pinfunction "7Q_16") (pintype "tri_state"))
      (node (ref "OUT1-2") (pin "13") (pinfunction "13_13") (pintype "passive"))
    )
    (net (code "60") (name "Net-(IC2A-8Q)") (class "Default")
      (node (ref "IC2") (pin "19") (pinfunction "8Q_19") (pintype "tri_state"))
      (node (ref "OUT1-2") (pin "15") (pinfunction "15_15") (pintype "passive"))
    )
    (net (code "61") (name "Net-(IC3A-1Q)") (class "Default")
      (node (ref "IC3") (pin "2") (pinfunction "1Q_2") (pintype "tri_state"))
      (node (ref "OUT3-4") (pin "2") (pinfunction "2_2") (pintype "passive"))
    )
    (net (code "62") (name "Net-(IC3A-2Q)") (class "Default")
      (node (ref "IC3") (pin "5") (pinfunction "2Q_5") (pintype "tri_state"))
      (node (ref "OUT3-4") (pin "4") (pinfunction "4_4") (pintype "passive"))
    )
    (net (code "63") (name "Net-(IC3A-3Q)") (class "Default")
      (node (ref "IC3") (pin "6") (pinfunction "3Q_6") (pintype "tri_state"))
      (node (ref "OUT3-4") (pin "6") (pinfunction "6_6") (pintype "passive"))
    )
    (net (code "64") (name "Net-(IC3A-4Q)") (class "Default")
      (node (ref "IC3") (pin "9") (pinfunction "4Q_9") (pintype "tri_state"))
      (node (ref "OUT3-4") (pin "8") (pinfunction "8_8") (pintype "passive"))
    )
    (net (code "65") (name "Net-(IC3A-5Q)") (class "Default")
      (node (ref "IC3") (pin "12") (pinfunction "5Q_12") (pintype "tri_state"))
      (node (ref "OUT3-4") (pin "1") (pinfunction "1_1") (pintype "passive"))
    )
    (net (code "66") (name "Net-(IC3A-6Q)") (class "Default")
      (node (ref "IC3") (pin "15") (pinfunction "6Q_15") (pintype "tri_state"))
      (node (ref "OUT3-4") (pin "3") (pinfunction "3_3") (pintype "passive"))
    )
    (net (code "67") (name "Net-(IC3A-7Q)") (class "Default")
      (node (ref "IC3") (pin "16") (pinfunction "7Q_16") (pintype "tri_state"))
      (node (ref "OUT3-4") (pin "5") (pinfunction "5_5") (pintype "passive"))
    )
    (net (code "68") (name "Net-(IC3A-8Q)") (class "Default")
      (node (ref "IC3") (pin "19") (pinfunction "8Q_19") (pintype "tri_state"))
      (node (ref "OUT3-4") (pin "7") (pinfunction "7_7") (pintype "passive"))
    )
    (net (code "69") (name "Net-(IC4A-1Q)") (class "Default")
      (node (ref "IC4") (pin "2") (pinfunction "1Q_2") (pintype "tri_state"))
      (node (ref "OUT3-4") (pin "10") (pinfunction "10_10") (pintype "passive"))
    )
    (net (code "70") (name "Net-(IC4A-2Q)") (class "Default")
      (node (ref "IC4") (pin "5") (pinfunction "2Q_5") (pintype "tri_state"))
      (node (ref "OUT3-4") (pin "12") (pinfunction "12_12") (pintype "passive"))
    )
    (net (code "71") (name "Net-(IC4A-3Q)") (class "Default")
      (node (ref "IC4") (pin "6") (pinfunction "3Q_6") (pintype "tri_state"))
      (node (ref "OUT3-4") (pin "14") (pinfunction "14_14") (pintype "passive"))
    )
    (net (code "72") (name "Net-(IC4A-4Q)") (class "Default")
      (node (ref "IC4") (pin "9") (pinfunction "4Q_9") (pintype "tri_state"))
      (node (ref "OUT3-4") (pin "16") (pinfunction "16_16") (pintype "passive"))
    )
    (net (code "73") (name "Net-(IC4A-5Q)") (class "Default")
      (node (ref "IC4") (pin "12") (pinfunction "5Q_12") (pintype "tri_state"))
      (node (ref "OUT3-4") (pin "9") (pinfunction "9_9") (pintype "passive"))
    )
    (net (code "74") (name "Net-(IC4A-6Q)") (class "Default")
      (node (ref "IC4") (pin "15") (pinfunction "6Q_15") (pintype "tri_state"))
      (node (ref "OUT3-4") (pin "11") (pinfunction "11_11") (pintype "passive"))
    )
    (net (code "75") (name "Net-(IC4A-7Q)") (class "Default")
      (node (ref "IC4") (pin "16") (pinfunction "7Q_16") (pintype "tri_state"))
      (node (ref "OUT3-4") (pin "13") (pinfunction "13_13") (pintype "passive"))
    )
    (net (code "76") (name "Net-(IC4A-8Q)") (class "Default")
      (node (ref "IC4") (pin "19") (pinfunction "8Q_19") (pintype "tri_state"))
      (node (ref "OUT3-4") (pin "15") (pinfunction "15_15") (pintype "passive"))
    )
    (net (code "77") (name "Net-(IC5A-1Q)") (class "Default")
      (node (ref "IC5") (pin "2") (pinfunction "1Q_2") (pintype "tri_state"))
      (node (ref "OUT5-6") (pin "2") (pinfunction "2_2") (pintype "passive"))
    )
    (net (code "78") (name "Net-(IC5A-2Q)") (class "Default")
      (node (ref "IC5") (pin "5") (pinfunction "2Q_5") (pintype "tri_state"))
      (node (ref "OUT5-6") (pin "4") (pinfunction "4_4") (pintype "passive"))
    )
    (net (code "79") (name "Net-(IC5A-3Q)") (class "Default")
      (node (ref "IC5") (pin "6") (pinfunction "3Q_6") (pintype "tri_state"))
      (node (ref "OUT5-6") (pin "6") (pinfunction "6_6") (pintype "passive"))
    )
    (net (code "80") (name "Net-(IC5A-4Q)") (class "Default")
      (node (ref "IC5") (pin "9") (pinfunction "4Q_9") (pintype "tri_state"))
      (node (ref "OUT5-6") (pin "8") (pinfunction "8_8") (pintype "passive"))
    )
    (net (code "81") (name "Net-(IC5A-5Q)") (class "Default")
      (node (ref "IC5") (pin "12") (pinfunction "5Q_12") (pintype "tri_state"))
      (node (ref "OUT5-6") (pin "1") (pinfunction "1_1") (pintype "passive"))
    )
    (net (code "82") (name "Net-(IC5A-6Q)") (class "Default")
      (node (ref "IC5") (pin "15") (pinfunction "6Q_15") (pintype "tri_state"))
      (node (ref "OUT5-6") (pin "3") (pinfunction "3_3") (pintype "passive"))
    )
    (net (code "83") (name "Net-(IC5A-7Q)") (class "Default")
      (node (ref "IC5") (pin "16") (pinfunction "7Q_16") (pintype "tri_state"))
      (node (ref "OUT5-6") (pin "5") (pinfunction "5_5") (pintype "passive"))
    )
    (net (code "84") (name "Net-(IC5A-8Q)") (class "Default")
      (node (ref "IC5") (pin "19") (pinfunction "8Q_19") (pintype "tri_state"))
      (node (ref "OUT5-6") (pin "7") (pinfunction "7_7") (pintype "passive"))
    )
    (net (code "85") (name "Net-(IC6A-1Q)") (class "Default")
      (node (ref "IC6") (pin "2") (pinfunction "1Q_2") (pintype "tri_state"))
      (node (ref "OUT5-6") (pin "10") (pinfunction "10_10") (pintype "passive"))
    )
    (net (code "86") (name "Net-(IC6A-2Q)") (class "Default")
      (node (ref "IC6") (pin "5") (pinfunction "2Q_5") (pintype "tri_state"))
      (node (ref "OUT5-6") (pin "12") (pinfunction "12_12") (pintype "passive"))
    )
    (net (code "87") (name "Net-(IC6A-3Q)") (class "Default")
      (node (ref "IC6") (pin "6") (pinfunction "3Q_6") (pintype "tri_state"))
      (node (ref "OUT5-6") (pin "14") (pinfunction "14_14") (pintype "passive"))
    )
    (net (code "88") (name "Net-(IC6A-4Q)") (class "Default")
      (node (ref "IC6") (pin "9") (pinfunction "4Q_9") (pintype "tri_state"))
      (node (ref "OUT5-6") (pin "16") (pinfunction "16_16") (pintype "passive"))
    )
    (net (code "89") (name "Net-(IC6A-5Q)") (class "Default")
      (node (ref "IC6") (pin "12") (pinfunction "5Q_12") (pintype "tri_state"))
      (node (ref "OUT5-6") (pin "9") (pinfunction "9_9") (pintype "passive"))
    )
    (net (code "90") (name "Net-(IC6A-6Q)") (class "Default")
      (node (ref "IC6") (pin "15") (pinfunction "6Q_15") (pintype "tri_state"))
      (node (ref "OUT5-6") (pin "11") (pinfunction "11_11") (pintype "passive"))
    )
    (net (code "91") (name "Net-(IC6A-7Q)") (class "Default")
      (node (ref "IC6") (pin "16") (pinfunction "7Q_16") (pintype "tri_state"))
      (node (ref "OUT5-6") (pin "13") (pinfunction "13_13") (pintype "passive"))
    )
    (net (code "92") (name "Net-(IC6A-8Q)") (class "Default")
      (node (ref "IC6") (pin "19") (pinfunction "8Q_19") (pintype "tri_state"))
      (node (ref "OUT5-6") (pin "15") (pinfunction "15_15") (pintype "passive"))
    )
    (net (code "93") (name "Net-(IC7A-1Q)") (class "Default")
      (node (ref "IC7") (pin "2") (pinfunction "1Q_2") (pintype "tri_state"))
      (node (ref "OUT7-8") (pin "2") (pinfunction "2_2") (pintype "passive"))
    )
    (net (code "94") (name "Net-(IC7A-2Q)") (class "Default")
      (node (ref "IC7") (pin "5") (pinfunction "2Q_5") (pintype "tri_state"))
      (node (ref "OUT7-8") (pin "4") (pinfunction "4_4") (pintype "passive"))
    )
    (net (code "95") (name "Net-(IC7A-3Q)") (class "Default")
      (node (ref "IC7") (pin "6") (pinfunction "3Q_6") (pintype "tri_state"))
      (node (ref "OUT7-8") (pin "6") (pinfunction "6_6") (pintype "passive"))
    )
    (net (code "96") (name "Net-(IC7A-4Q)") (class "Default")
      (node (ref "IC7") (pin "9") (pinfunction "4Q_9") (pintype "tri_state"))
      (node (ref "OUT7-8") (pin "8") (pinfunction "8_8") (pintype "passive"))
    )
    (net (code "97") (name "Net-(IC7A-5Q)") (class "Default")
      (node (ref "IC7") (pin "12") (pinfunction "5Q_12") (pintype "tri_state"))
      (node (ref "OUT7-8") (pin "1") (pinfunction "1_1") (pintype "passive"))
    )
    (net (code "98") (name "Net-(IC7A-6Q)") (class "Default")
      (node (ref "IC7") (pin "15") (pinfunction "6Q_15") (pintype "tri_state"))
      (node (ref "OUT7-8") (pin "3") (pinfunction "3_3") (pintype "passive"))
    )
    (net (code "99") (name "Net-(IC7A-7Q)") (class "Default")
      (node (ref "IC7") (pin "16") (pinfunction "7Q_16") (pintype "tri_state"))
      (node (ref "OUT7-8") (pin "5") (pinfunction "5_5") (pintype "passive"))
    )
    (net (code "100") (name "Net-(IC7A-8Q)") (class "Default")
      (node (ref "IC7") (pin "19") (pinfunction "8Q_19") (pintype "tri_state"))
      (node (ref "OUT7-8") (pin "7") (pinfunction "7_7") (pintype "passive"))
    )
    (net (code "101") (name "Net-(IC8A-1Q)") (class "Default")
      (node (ref "IC8") (pin "2") (pinfunction "1Q_2") (pintype "tri_state"))
      (node (ref "OUT7-8") (pin "10") (pinfunction "10_10") (pintype "passive"))
    )
    (net (code "102") (name "Net-(IC8A-2Q)") (class "Default")
      (node (ref "IC8") (pin "5") (pinfunction "2Q_5") (pintype "tri_state"))
      (node (ref "OUT7-8") (pin "12") (pinfunction "12_12") (pintype "passive"))
    )
    (net (code "103") (name "Net-(IC8A-3Q)") (class "Default")
      (node (ref "IC8") (pin "6") (pinfunction "3Q_6") (pintype "tri_state"))
      (node (ref "OUT7-8") (pin "14") (pinfunction "14_14") (pintype "passive"))
    )
    (net (code "104") (name "Net-(IC8A-4Q)") (class "Default")
      (node (ref "IC8") (pin "9") (pinfunction "4Q_9") (pintype "tri_state"))
      (node (ref "OUT7-8") (pin "16") (pinfunction "16_16") (pintype "passive"))
    )
    (net (code "105") (name "Net-(IC8A-5Q)") (class "Default")
      (node (ref "IC8") (pin "12") (pinfunction "5Q_12") (pintype "tri_state"))
      (node (ref "OUT7-8") (pin "9") (pinfunction "9_9") (pintype "passive"))
    )
    (net (code "106") (name "Net-(IC8A-6Q)") (class "Default")
      (node (ref "IC8") (pin "15") (pinfunction "6Q_15") (pintype "tri_state"))
      (node (ref "OUT7-8") (pin "11") (pinfunction "11_11") (pintype "passive"))
    )
    (net (code "107") (name "Net-(IC8A-7Q)") (class "Default")
      (node (ref "IC8") (pin "16") (pinfunction "7Q_16") (pintype "tri_state"))
      (node (ref "OUT7-8") (pin "13") (pinfunction "13_13") (pintype "passive"))
    )
    (net (code "108") (name "Net-(IC8A-8Q)") (class "Default")
      (node (ref "IC8") (pin "19") (pinfunction "8Q_19") (pintype "tri_state"))
      (node (ref "OUT7-8") (pin "15") (pinfunction "15_15") (pintype "passive"))
    )
    (net (code "109") (name "Net-(IC11A-1D)") (class "Default")
      (node (ref "IC11") (pin "3") (pinfunction "1D_3") (pintype "input"))
      (node (ref "IN1-2") (pin "2") (pinfunction "2_2") (pintype "passive"))
    )
    (net (code "110") (name "Net-(IC11A-2D)") (class "Default")
      (node (ref "IC11") (pin "4") (pinfunction "2D_4") (pintype "input"))
      (node (ref "IN1-2") (pin "4") (pinfunction "4_4") (pintype "passive"))
    )
    (net (code "111") (name "Net-(IC11A-3D)") (class "Default")
      (node (ref "IC11") (pin "7") (pinfunction "3D_7") (pintype "input"))
      (node (ref "IN1-2") (pin "6") (pinfunction "6_6") (pintype "passive"))
    )
    (net (code "112") (name "Net-(IC11A-4D)") (class "Default")
      (node (ref "IC11") (pin "8") (pinfunction "4D_8") (pintype "input"))
      (node (ref "IN1-2") (pin "8") (pinfunction "8_8") (pintype "passive"))
    )
    (net (code "113") (name "Net-(IC11A-5D)") (class "Default")
      (node (ref "IC11") (pin "13") (pinfunction "5D_13") (pintype "input"))
      (node (ref "IN1-2") (pin "1") (pinfunction "1_1") (pintype "passive"))
    )
    (net (code "114") (name "Net-(IC11A-6D)") (class "Default")
      (node (ref "IC11") (pin "14") (pinfunction "6D_14") (pintype "input"))
      (node (ref "IN1-2") (pin "3") (pinfunction "3_3") (pintype "passive"))
    )
    (net (code "115") (name "Net-(IC11A-7D)") (class "Default")
      (node (ref "IC11") (pin "17") (pinfunction "7D_17") (pintype "input"))
      (node (ref "IN1-2") (pin "5") (pinfunction "5_5") (pintype "passive"))
    )
    (net (code "116") (name "Net-(IC11A-8D)") (class "Default")
      (node (ref "IC11") (pin "18") (pinfunction "8D_18") (pintype "input"))
      (node (ref "IN1-2") (pin "7") (pinfunction "7_7") (pintype "passive"))
    )
    (net (code "117") (name "Net-(IC12A-1D)") (class "Default")
      (node (ref "IC12") (pin "3") (pinfunction "1D_3") (pintype "input"))
      (node (ref "IN1-2") (pin "10") (pinfunction "10_10") (pintype "passive"))
    )
    (net (code "118") (name "Net-(IC12A-2D)") (class "Default")
      (node (ref "IC12") (pin "4") (pinfunction "2D_4") (pintype "input"))
      (node (ref "IN1-2") (pin "12") (pinfunction "12_12") (pintype "passive"))
    )
    (net (code "119") (name "Net-(IC12A-3D)") (class "Default")
      (node (ref "IC12") (pin "7") (pinfunction "3D_7") (pintype "input"))
      (node (ref "IN1-2") (pin "14") (pinfunction "14_14") (pintype "passive"))
    )
    (net (code "120") (name "Net-(IC12A-4D)") (class "Default")
      (node (ref "IC12") (pin "8") (pinfunction "4D_8") (pintype "input"))
      (node (ref "IN1-2") (pin "16") (pinfunction "16_16") (pintype "passive"))
    )
    (net (code "121") (name "Net-(IC12A-5D)") (class "Default")
      (node (ref "IC12") (pin "13") (pinfunction "5D_13") (pintype "input"))
      (node (ref "IN1-2") (pin "9") (pinfunction "9_9") (pintype "passive"))
    )
    (net (code "122") (name "Net-(IC12A-6D)") (class "Default")
      (node (ref "IC12") (pin "14") (pinfunction "6D_14") (pintype "input"))
      (node (ref "IN1-2") (pin "11") (pinfunction "11_11") (pintype "passive"))
    )
    (net (code "123") (name "Net-(IC12A-7D)") (class "Default")
      (node (ref "IC12") (pin "17") (pinfunction "7D_17") (pintype "input"))
      (node (ref "IN1-2") (pin "13") (pinfunction "13_13") (pintype "passive"))
    )
    (net (code "124") (name "Net-(IC12A-8D)") (class "Default")
      (node (ref "IC12") (pin "18") (pinfunction "8D_18") (pintype "input"))
      (node (ref "IN1-2") (pin "15") (pinfunction "15_15") (pintype "passive"))
    )
    (net (code "125") (name "Net-(IC13A-1D)") (class "Default")
      (node (ref "IC13") (pin "3") (pinfunction "1D_3") (pintype "input"))
      (node (ref "IN3-4") (pin "2") (pinfunction "2_2") (pintype "passive"))
    )
    (net (code "126") (name "Net-(IC13A-2D)") (class "Default")
      (node (ref "IC13") (pin "4") (pinfunction "2D_4") (pintype "input"))
      (node (ref "IN3-4") (pin "4") (pinfunction "4_4") (pintype "passive"))
    )
    (net (code "127") (name "Net-(IC13A-3D)") (class "Default")
      (node (ref "IC13") (pin "7") (pinfunction "3D_7") (pintype "input"))
      (node (ref "IN3-4") (pin "6") (pinfunction "6_6") (pintype "passive"))
    )
    (net (code "128") (name "Net-(IC13A-4D)") (class "Default")
      (node (ref "IC13") (pin "8") (pinfunction "4D_8") (pintype "input"))
      (node (ref "IN3-4") (pin "8") (pinfunction "8_8") (pintype "passive"))
    )
    (net (code "129") (name "Net-(IC13A-5D)") (class "Default")
      (node (ref "IC13") (pin "13") (pinfunction "5D_13") (pintype "input"))
      (node (ref "IN3-4") (pin "1") (pinfunction "1_1") (pintype "passive"))
    )
    (net (code "130") (name "Net-(IC13A-6D)") (class "Default")
      (node (ref "IC13") (pin "14") (pinfunction "6D_14") (pintype "input"))
      (node (ref "IN3-4") (pin "3") (pinfunction "3_3") (pintype "passive"))
    )
    (net (code "131") (name "Net-(IC13A-7D)") (class "Default")
      (node (ref "IC13") (pin "17") (pinfunction "7D_17") (pintype "input"))
      (node (ref "IN3-4") (pin "5") (pinfunction "5_5") (pintype "passive"))
    )
    (net (code "132") (name "Net-(IC13A-8D)") (class "Default")
      (node (ref "IC13") (pin "18") (pinfunction "8D_18") (pintype "input"))
      (node (ref "IN3-4") (pin "7") (pinfunction "7_7") (pintype "passive"))
    )
    (net (code "133") (name "Net-(IC14A-1D)") (class "Default")
      (node (ref "IC14") (pin "3") (pinfunction "1D_3") (pintype "input"))
      (node (ref "IN3-4") (pin "10") (pinfunction "10_10") (pintype "passive"))
    )
    (net (code "134") (name "Net-(IC14A-2D)") (class "Default")
      (node (ref "IC14") (pin "4") (pinfunction "2D_4") (pintype "input"))
      (node (ref "IN3-4") (pin "12") (pinfunction "12_12") (pintype "passive"))
    )
    (net (code "135") (name "Net-(IC14A-3D)") (class "Default")
      (node (ref "IC14") (pin "7") (pinfunction "3D_7") (pintype "input"))
      (node (ref "IN3-4") (pin "14") (pinfunction "14_14") (pintype "passive"))
    )
    (net (code "136") (name "Net-(IC14A-4D)") (class "Default")
      (node (ref "IC14") (pin "8") (pinfunction "4D_8") (pintype "input"))
      (node (ref "IN3-4") (pin "16") (pinfunction "16_16") (pintype "passive"))
    )
    (net (code "137") (name "Net-(IC14A-5D)") (class "Default")
      (node (ref "IC14") (pin "13") (pinfunction "5D_13") (pintype "input"))
      (node (ref "IN3-4") (pin "9") (pinfunction "9_9") (pintype "passive"))
    )
    (net (code "138") (name "Net-(IC14A-6D)") (class "Default")
      (node (ref "IC14") (pin "14") (pinfunction "6D_14") (pintype "input"))
      (node (ref "IN3-4") (pin "11") (pinfunction "11_11") (pintype "passive"))
    )
    (net (code "139") (name "Net-(IC14A-7D)") (class "Default")
      (node (ref "IC14") (pin "17") (pinfunction "7D_17") (pintype "input"))
      (node (ref "IN3-4") (pin "13") (pinfunction "13_13") (pintype "passive"))
    )
    (net (code "140") (name "Net-(IC14A-8D)") (class "Default")
      (node (ref "IC14") (pin "18") (pinfunction "8D_18") (pintype "input"))
      (node (ref "IN3-4") (pin "15") (pinfunction "15_15") (pintype "passive"))
    )
    (net (code "141") (name "Net-(IC15A-1D)") (class "Default")
      (node (ref "IC15") (pin "3") (pinfunction "1D_3") (pintype "input"))
      (node (ref "IN5-6") (pin "2") (pinfunction "2_2") (pintype "passive"))
    )
    (net (code "142") (name "Net-(IC15A-2D)") (class "Default")
      (node (ref "IC15") (pin "4") (pinfunction "2D_4") (pintype "input"))
      (node (ref "IN5-6") (pin "4") (pinfunction "4_4") (pintype "passive"))
    )
    (net (code "143") (name "Net-(IC15A-3D)") (class "Default")
      (node (ref "IC15") (pin "7") (pinfunction "3D_7") (pintype "input"))
      (node (ref "IN5-6") (pin "6") (pinfunction "6_6") (pintype "passive"))
    )
    (net (code "144") (name "Net-(IC15A-4D)") (class "Default")
      (node (ref "IC15") (pin "8") (pinfunction "4D_8") (pintype "input"))
      (node (ref "IN5-6") (pin "8") (pinfunction "8_8") (pintype "passive"))
    )
    (net (code "145") (name "Net-(IC15A-5D)") (class "Default")
      (node (ref "IC15") (pin "13") (pinfunction "5D_13") (pintype "input"))
      (node (ref "IN5-6") (pin "1") (pinfunction "1_1") (pintype "passive"))
    )
    (net (code "146") (name "Net-(IC15A-6D)") (class "Default")
      (node (ref "IC15") (pin "14") (pinfunction "6D_14") (pintype "input"))
      (node (ref "IN5-6") (pin "3") (pinfunction "3_3") (pintype "passive"))
    )
    (net (code "147") (name "Net-(IC15A-7D)") (class "Default")
      (node (ref "IC15") (pin "17") (pinfunction "7D_17") (pintype "input"))
      (node (ref "IN5-6") (pin "5") (pinfunction "5_5") (pintype "passive"))
    )
    (net (code "148") (name "Net-(IC15A-8D)") (class "Default")
      (node (ref "IC15") (pin "18") (pinfunction "8D_18") (pintype "input"))
      (node (ref "IN5-6") (pin "7") (pinfunction "7_7") (pintype "passive"))
    )
    (net (code "149") (name "Net-(IC16A-1D)") (class "Default")
      (node (ref "IC16") (pin "3") (pinfunction "1D_3") (pintype "input"))
      (node (ref "IN5-6") (pin "10") (pinfunction "10_10") (pintype "passive"))
    )
    (net (code "150") (name "Net-(IC16A-2D)") (class "Default")
      (node (ref "IC16") (pin "4") (pinfunction "2D_4") (pintype "input"))
      (node (ref "IN5-6") (pin "12") (pinfunction "12_12") (pintype "passive"))
    )
    (net (code "151") (name "Net-(IC16A-3D)") (class "Default")
      (node (ref "IC16") (pin "7") (pinfunction "3D_7") (pintype "input"))
      (node (ref "IN5-6") (pin "14") (pinfunction "14_14") (pintype "passive"))
    )
    (net (code "152") (name "Net-(IC16A-4D)") (class "Default")
      (node (ref "IC16") (pin "8") (pinfunction "4D_8") (pintype "input"))
      (node (ref "IN5-6") (pin "16") (pinfunction "16_16") (pintype "passive"))
    )
    (net (code "153") (name "Net-(IC16A-5D)") (class "Default")
      (node (ref "IC16") (pin "13") (pinfunction "5D_13") (pintype "input"))
      (node (ref "IN5-6") (pin "9") (pinfunction "9_9") (pintype "passive"))
    )
    (net (code "154") (name "Net-(IC16A-6D)") (class "Default")
      (node (ref "IC16") (pin "14") (pinfunction "6D_14") (pintype "input"))
      (node (ref "IN5-6") (pin "11") (pinfunction "11_11") (pintype "passive"))
    )
    (net (code "155") (name "Net-(IC16A-7D)") (class "Default")
      (node (ref "IC16") (pin "17") (pinfunction "7D_17") (pintype "input"))
      (node (ref "IN5-6") (pin "13") (pinfunction "13_13") (pintype "passive"))
    )
    (net (code "156") (name "Net-(IC16A-8D)") (class "Default")
      (node (ref "IC16") (pin "18") (pinfunction "8D_18") (pintype "input"))
      (node (ref "IN5-6") (pin "15") (pinfunction "15_15") (pintype "passive"))
    )
    (net (code "157") (name "Net-(IC17A-EXTAL)") (class "Default")
      (node (ref "C2") (pin "1") (pinfunction "1_1") (pintype "passive"))
      (node (ref "IC17") (pin "39") (pinfunction "EXTAL_39") (pintype "input"))
      (node (ref "Q1") (pin "1") (pinfunction "1_1") (pintype "passive"))
    )
    (net (code "158") (name "Net-(IC17A-XTAL)") (class "Default")
      (node (ref "C1") (pin "2") (pinfunction "2_2") (pintype "passive"))
      (node (ref "IC17") (pin "38") (pinfunction "XTAL_38") (pintype "input"))
      (node (ref "Q1") (pin "2") (pinfunction "2_2") (pintype "passive"))
    )
    (net (code "159") (name "Net-(IC18A-I0)") (class "Default")
      (node (ref "C3") (pin "1") (pinfunction "1_1") (pintype "passive"))
      (node (ref "IC18") (pin "1") (pinfunction "I0_1") (pintype "input"))
      (node (ref "R1") (pin "1") (pinfunction "1_1") (pintype "passive"))
    )
    (net (code "160") (name "Net-(IC18A-I1)") (class "Default")
      (node (ref "IC18") (pin "2") (pinfunction "I1_2") (pintype "input"))
      (node (ref "JP1") (pin "2") (pinfunction "2_2") (pintype "passive"))
      (node (ref "R2") (pin "1") (pinfunction "1_1") (pintype "passive"))
    )
    (net (code "161") (name "Net-(IC18A-O)") (class "Default")
      (node (ref "IC18") (pin "3") (pinfunction "O_3") (pintype "output"))
      (node (ref "IC18") (pin "4") (pinfunction "I0_4") (pintype "input"))
      (node (ref "IC18") (pin "5") (pinfunction "I1_5") (pintype "input"))
    )
    (net (code "162") (name "Net-(IC18C-O)") (class "Default")
      (node (ref "IC18") (pin "8") (pinfunction "O_8") (pintype "output"))
      (node (ref "IC28") (pin "4") (pinfunction "G2A_4") (pintype "input"))
    )
    (net (code "163") (name "Net-(IC18D-I0)") (class "Default")
      (node (ref "IC18") (pin "12") (pinfunction "I0_12") (pintype "input"))
      (node (ref "IC18") (pin "13") (pinfunction "I1_13") (pintype "input"))
      (node (ref "IC21") (pin "5") (pinfunction "RTS_5") (pintype "output"))
    )
    (net (code "164") (name "Net-(IC18D-O)") (class "Default")
      (node (ref "IC18") (pin "11") (pinfunction "O_11") (pintype "output"))
      (node (ref "LED1") (pin "K") (pinfunction "C_K") (pintype "passive"))
    )
    (net (code "165") (name "Net-(IC19A-G2B)") (class "Default")
      (node (ref "IC19") (pin "5") (pinfunction "G2B_5") (pintype "input"))
      (node (ref "IC28") (pin "15") (pinfunction "Y0_15") (pintype "output"))
    )
    (net (code "166") (name "Net-(IC20A-C1+)") (class "Default")
      (node (ref "C8") (pin "1") (pinfunction "1_1") (pintype "passive"))
      (node (ref "IC20") (pin "1") (pinfunction "C1+_1") (pintype "bidirectional"))
    )
    (net (code "167") (name "Net-(IC20A-C1-)") (class "Default")
      (node (ref "C8") (pin "2") (pinfunction "2_2") (pintype "passive"))
      (node (ref "IC20") (pin "3") (pinfunction "C1-_3") (pintype "bidirectional"))
    )
    (net (code "168") (name "Net-(IC20A-C2+)") (class "Default")
      (node (ref "C9") (pin "1") (pinfunction "1_1") (pintype "passive"))
      (node (ref "IC20") (pin "4") (pinfunction "C2+_4") (pintype "bidirectional"))
    )
    (net (code "169") (name "Net-(IC20A-C2-)") (class "Default")
      (node (ref "C9") (pin "2") (pinfunction "2_2") (pintype "passive"))
      (node (ref "IC20") (pin "5") (pinfunction "C2-_5") (pintype "bidirectional"))
    )
    (net (code "170") (name "Net-(IC20A-R2IN)") (class "Default")
      (node (ref "IC20") (pin "7") (pinfunction "T2OUT_7") (pintype "output"))
      (node (ref "IC20") (pin "8") (pinfunction "R2IN_8") (pintype "input"))
    )
    (net (code "171") (name "Net-(IC20A-V+)") (class "Default")
      (node (ref "C10") (pin "2") (pinfunction "2_2") (pintype "passive"))
      (node (ref "IC20") (pin "2") (pinfunction "V+_2") (pintype "bidirectional"))
    )
    (net (code "172") (name "Net-(IC20A-V-)") (class "Default")
      (node (ref "C11") (pin "1") (pinfunction "1_1") (pintype "passive"))
      (node (ref "IC20") (pin "6") (pinfunction "V-_6") (pintype "bidirectional"))
    )
    (net (code "173") (name "Net-(IC21A-CTS)") (class "Default")
      (node (ref "IC21") (pin "24") (pinfunction "CTS_24") (pintype "input"))
      (node (ref "JP2") (pin "1") (pinfunction "1_1") (pintype "passive"))
      (node (ref "R13") (pin "2") (pinfunction "2_2") (pintype "passive"))
    )
    (net (code "174") (name "Net-(IC21A-RXCLK)") (class "Default")
      (node (ref "IC21") (pin "3") (pinfunction "RXCLK_3") (pintype "input"))
      (node (ref "IC21") (pin "4") (pinfunction "TXCLK_4") (pintype "input"))
      (node (ref "IC27") (pin "5") (pinfunction "Q_5") (pintype "output"))
    )
    (net (code "175") (name "Net-(IC24A-CA1)") (class "Default")
      (node (ref "IC24") (pin "40") (pinfunction "CA1_40") (pintype "input"))
      (node (ref "IC27") (pin "9") (pinfunction "Q_9") (pintype "output"))
    )
    (net (code "176") (name "Net-(IC24A-CA2)") (class "Default")
      (node (ref "IC24") (pin "39") (pinfunction "CA2_39") (pintype "bidirectional"))
      (node (ref "IC25") (pin "1") (pinfunction "DIR_1") (pintype "input"))
    )
    (net (code "177") (name "Net-(IC24A-CB2)") (class "Default")
      (node (ref "IC24") (pin "19") (pinfunction "CB2_19") (pintype "bidirectional"))
      (node (ref "IC26") (pin "1") (pinfunction "DIR_1") (pintype "input"))
    )
    (net (code "178") (name "Net-(IC24A-PA0)") (class "Default")
      (node (ref "IC24") (pin "2") (pinfunction "PA0_2") (pintype "bidirectional"))
      (node (ref "IC25") (pin "2") (pinfunction "A1_2") (pintype "bidirectional"))
    )
    (net (code "179") (name "Net-(IC24A-PA1)") (class "Default")
      (node (ref "IC24") (pin "3") (pinfunction "PA1_3") (pintype "bidirectional"))
      (node (ref "IC25") (pin "3") (pinfunction "A2_3") (pintype "bidirectional"))
    )
    (net (code "180") (name "Net-(IC24A-PA2)") (class "Default")
      (node (ref "IC24") (pin "4") (pinfunction "PA2_4") (pintype "bidirectional"))
      (node (ref "IC25") (pin "4") (pinfunction "A3_4") (pintype "bidirectional"))
    )
    (net (code "181") (name "Net-(IC24A-PA3)") (class "Default")
      (node (ref "IC24") (pin "5") (pinfunction "PA3_5") (pintype "bidirectional"))
      (node (ref "IC25") (pin "5") (pinfunction "A4_5") (pintype "bidirectional"))
    )
    (net (code "182") (name "Net-(IC24A-PA4)") (class "Default")
      (node (ref "IC24") (pin "6") (pinfunction "PA4_6") (pintype "bidirectional"))
      (node (ref "IC25") (pin "6") (pinfunction "A5_6") (pintype "bidirectional"))
    )
    (net (code "183") (name "Net-(IC24A-PA5)") (class "Default")
      (node (ref "IC24") (pin "7") (pinfunction "PA5_7") (pintype "bidirectional"))
      (node (ref "IC25") (pin "7") (pinfunction "A6_7") (pintype "bidirectional"))
    )
    (net (code "184") (name "Net-(IC24A-PA6)") (class "Default")
      (node (ref "IC24") (pin "8") (pinfunction "PA6_8") (pintype "bidirectional"))
      (node (ref "IC25") (pin "8") (pinfunction "A7_8") (pintype "bidirectional"))
    )
    (net (code "185") (name "Net-(IC24A-PA7)") (class "Default")
      (node (ref "IC24") (pin "9") (pinfunction "PA7_9") (pintype "bidirectional"))
      (node (ref "IC25") (pin "9") (pinfunction "A8_9") (pintype "bidirectional"))
    )
    (net (code "186") (name "Net-(IC24A-PB0)") (class "Default")
      (node (ref "IC24") (pin "10") (pinfunction "PB0_10") (pintype "bidirectional"))
      (node (ref "IC26") (pin "2") (pinfunction "A1_2") (pintype "bidirectional"))
    )
    (net (code "187") (name "Net-(IC24A-PB1)") (class "Default")
      (node (ref "IC24") (pin "11") (pinfunction "PB1_11") (pintype "bidirectional"))
      (node (ref "IC26") (pin "3") (pinfunction "A2_3") (pintype "bidirectional"))
    )
    (net (code "188") (name "Net-(IC24A-PB2)") (class "Default")
      (node (ref "IC24") (pin "12") (pinfunction "PB2_12") (pintype "bidirectional"))
      (node (ref "IC26") (pin "4") (pinfunction "A3_4") (pintype "bidirectional"))
    )
    (net (code "189") (name "Net-(IC24A-PB3)") (class "Default")
      (node (ref "IC24") (pin "13") (pinfunction "PB3_13") (pintype "bidirectional"))
      (node (ref "IC26") (pin "5") (pinfunction "A4_5") (pintype "bidirectional"))
    )
    (net (code "190") (name "Net-(IC24A-PB4)") (class "Default")
      (node (ref "IC24") (pin "14") (pinfunction "PB4_14") (pintype "bidirectional"))
      (node (ref "IC26") (pin "6") (pinfunction "A5_6") (pintype "bidirectional"))
    )
    (net (code "191") (name "Net-(IC24A-PB5)") (class "Default")
      (node (ref "IC24") (pin "15") (pinfunction "PB5_15") (pintype "bidirectional"))
      (node (ref "IC26") (pin "7") (pinfunction "A6_7") (pintype "bidirectional"))
    )
    (net (code "192") (name "Net-(IC24A-PB6)") (class "Default")
      (node (ref "IC24") (pin "16") (pinfunction "PB6_16") (pintype "bidirectional"))
      (node (ref "IC26") (pin "8") (pinfunction "A7_8") (pintype "bidirectional"))
    )
    (net (code "193") (name "Net-(IC24A-PB7)") (class "Default")
      (node (ref "IC24") (pin "17") (pinfunction "PB7_17") (pintype "bidirectional"))
      (node (ref "IC26") (pin "9") (pinfunction "A8_9") (pintype "bidirectional"))
    )
    (net (code "194") (name "Net-(IC27A-CV)") (class "Default")
      (node (ref "C7") (pin "1") (pinfunction "1_1") (pintype "passive"))
      (node (ref "IC27") (pin "3") (pinfunction "CV_3") (pintype "input"))
    )
    (net (code "195") (name "Net-(IC27A-DIS)") (class "Default")
      (node (ref "IC27") (pin "1") (pinfunction "DIS_1") (pintype "input"))
      (node (ref "R10") (pin "2") (pinfunction "2_2") (pintype "passive"))
      (node (ref "R9") (pin "1") (pinfunction "1_1") (pintype "passive"))
    )
    (net (code "196") (name "Net-(IC27A-THR)") (class "Default")
      (node (ref "C6") (pin "1") (pinfunction "1_1") (pintype "passive"))
      (node (ref "IC27") (pin "2") (pinfunction "THR_2") (pintype "input"))
      (node (ref "IC27") (pin "6") (pinfunction "TR_6") (pintype "input"))
      (node (ref "R11") (pin "A") (pinfunction "A_A") (pintype "passive"))
    )
    (net (code "197") (name "Net-(IC27B-CV)") (class "Default")
      (node (ref "C5") (pin "1") (pinfunction "1_1") (pintype "passive"))
      (node (ref "IC27") (pin "11") (pinfunction "CV_11") (pintype "input"))
    )
    (net (code "198") (name "Net-(IC27B-DIS)") (class "Default")
      (node (ref "IC27") (pin "13") (pinfunction "DIS_13") (pintype "input"))
      (node (ref "R3") (pin "1") (pinfunction "1_1") (pintype "passive"))
      (node (ref "R4") (pin "2") (pinfunction "2_2") (pintype "passive"))
    )
    (net (code "199") (name "Net-(IC27B-THR)") (class "Default")
      (node (ref "C4") (pin "1") (pinfunction "1_1") (pintype "passive"))
      (node (ref "IC27") (pin "12") (pinfunction "THR_12") (pintype "input"))
      (node (ref "IC27") (pin "8") (pinfunction "TR_8") (pintype "input"))
      (node (ref "R4") (pin "1") (pinfunction "1_1") (pintype "passive"))
    )
    (net (code "200") (name "Net-(LED1-PadA)") (class "Default")
      (node (ref "LED1") (pin "A") (pinfunction "A_A") (pintype "passive"))
      (node (ref "R12") (pin "1") (pinfunction "1_1") (pintype "passive"))
    )
    (net (code "201") (name "Net-(R10-Pad1)") (class "Default")
      (node (ref "R10") (pin "1") (pinfunction "1_1") (pintype "passive"))
      (node (ref "R11") (pin "E") (pinfunction "E_E") (pintype "passive"))
    )
    (net (code "202") (name "Net-(X1-Pad4)") (class "Default")
      (node (ref "X1") (pin "4") (pinfunction "4_4") (pintype "passive"))
      (node (ref "X1") (pin "6") (pinfunction "6_6") (pintype "passive"))
    )
    (net (code "203") (name "Net-(X1-Pad5)") (class "Default")
      (node (ref "X1") (pin "5") (pinfunction "5_5") (pintype "passive"))
      (node (ref "X1") (pin "G1") (pinfunction "G1_G1") (pintype "passive"))
      (node (ref "X1") (pin "G2") (pinfunction "G2_G2") (pintype "passive"))
    )
    (net (code "204") (name "Net-(X1-Pad7)") (class "Default")
      (node (ref "X1") (pin "7") (pinfunction "7_7") (pintype "passive"))
      (node (ref "X1") (pin "8") (pinfunction "8_8") (pintype "passive"))
    )
    (net (code "205") (name "OUT00") (class "Default")
      (node (ref "IC1") (pin "11") (pinfunction "CLK_11") (pintype "input"))
      (node (ref "IC10") (pin "1") (pinfunction "0_1") (pintype "output"))
    )
    (net (code "206") (name "OUT01") (class "Default")
      (node (ref "IC10") (pin "2") (pinfunction "1_2") (pintype "output"))
      (node (ref "IC2") (pin "11") (pinfunction "CLK_11") (pintype "input"))
    )
    (net (code "207") (name "OUT02") (class "Default")
      (node (ref "IC10") (pin "3") (pinfunction "2_3") (pintype "output"))
      (node (ref "IC3") (pin "11") (pinfunction "CLK_11") (pintype "input"))
    )
    (net (code "208") (name "OUT03") (class "Default")
      (node (ref "IC10") (pin "4") (pinfunction "3_4") (pintype "output"))
      (node (ref "IC4") (pin "11") (pinfunction "CLK_11") (pintype "input"))
    )
    (net (code "209") (name "OUT04") (class "Default")
      (node (ref "IC10") (pin "5") (pinfunction "4_5") (pintype "output"))
      (node (ref "IC5") (pin "11") (pinfunction "CLK_11") (pintype "input"))
    )
    (net (code "210") (name "OUT05") (class "Default")
      (node (ref "IC10") (pin "6") (pinfunction "5_6") (pintype "output"))
      (node (ref "IC6") (pin "11") (pinfunction "CLK_11") (pintype "input"))
    )
    (net (code "211") (name "OUT06") (class "Default")
      (node (ref "IC10") (pin "7") (pinfunction "6_7") (pintype "output"))
      (node (ref "IC7") (pin "11") (pinfunction "CLK_11") (pintype "input"))
    )
    (net (code "212") (name "OUT07") (class "Default")
      (node (ref "IC10") (pin "8") (pinfunction "7_8") (pintype "output"))
      (node (ref "IC8") (pin "11") (pinfunction "CLK_11") (pintype "input"))
    )
    (net (code "213") (name "OUT08") (class "Default")
      (node (ref "IC10") (pin "9") (pinfunction "8_9") (pintype "output"))
    )
    (net (code "214") (name "OUT09") (class "Default")
      (node (ref "IC10") (pin "10") (pinfunction "9_10") (pintype "output"))
    )
    (net (code "215") (name "OUT10") (class "Default")
      (node (ref "IC10") (pin "11") (pinfunction "10_11") (pintype "output"))
    )
    (net (code "216") (name "OUT11") (class "Default")
      (node (ref "IC10") (pin "13") (pinfunction "11_13") (pintype "output"))
    )
    (net (code "217") (name "OUT12") (class "Default")
      (node (ref "IC10") (pin "14") (pinfunction "12_14") (pintype "output"))
    )
    (net (code "218") (name "OUT13") (class "Default")
      (node (ref "IC10") (pin "15") (pinfunction "13_15") (pintype "output"))
    )
    (net (code "219") (name "OUT14") (class "Default")
      (node (ref "IC10") (pin "16") (pinfunction "14_16") (pintype "output"))
    )
    (net (code "220") (name "OUT15") (class "Default")
      (node (ref "IC10") (pin "17") (pinfunction "15_17") (pintype "output"))
    )
    (net (code "221") (name "PIA-A0") (class "Default")
      (node (ref "IC1") (pin "3") (pinfunction "1D_3") (pintype "input"))
      (node (ref "IC11") (pin "2") (pinfunction "1Q_2") (pintype "tri_state"))
      (node (ref "IC12") (pin "2") (pinfunction "1Q_2") (pintype "tri_state"))
      (node (ref "IC13") (pin "2") (pinfunction "1Q_2") (pintype "tri_state"))
      (node (ref "IC14") (pin "2") (pinfunction "1Q_2") (pintype "tri_state"))
      (node (ref "IC15") (pin "2") (pinfunction "1Q_2") (pintype "tri_state"))
      (node (ref "IC16") (pin "2") (pinfunction "1Q_2") (pintype "tri_state"))
      (node (ref "IC2") (pin "3") (pinfunction "1D_3") (pintype "input"))
      (node (ref "IC25") (pin "18") (pinfunction "B1_18") (pintype "bidirectional"))
      (node (ref "IC3") (pin "3") (pinfunction "1D_3") (pintype "input"))
      (node (ref "IC4") (pin "3") (pinfunction "1D_3") (pintype "input"))
      (node (ref "IC5") (pin "3") (pinfunction "1D_3") (pintype "input"))
      (node (ref "IC6") (pin "3") (pinfunction "1D_3") (pintype "input"))
      (node (ref "IC7") (pin "3") (pinfunction "1D_3") (pintype "input"))
      (node (ref "IC8") (pin "3") (pinfunction "1D_3") (pintype "input"))
      (node (ref "SV9") (pin "1") (pinfunction "1_1") (pintype "passive"))
    )
    (net (code "222") (name "PIA-A1") (class "Default")
      (node (ref "IC1") (pin "4") (pinfunction "2D_4") (pintype "input"))
      (node (ref "IC11") (pin "5") (pinfunction "2Q_5") (pintype "tri_state"))
      (node (ref "IC12") (pin "5") (pinfunction "2Q_5") (pintype "tri_state"))
      (node (ref "IC13") (pin "5") (pinfunction "2Q_5") (pintype "tri_state"))
      (node (ref "IC14") (pin "5") (pinfunction "2Q_5") (pintype "tri_state"))
      (node (ref "IC15") (pin "5") (pinfunction "2Q_5") (pintype "tri_state"))
      (node (ref "IC16") (pin "5") (pinfunction "2Q_5") (pintype "tri_state"))
      (node (ref "IC2") (pin "4") (pinfunction "2D_4") (pintype "input"))
      (node (ref "IC25") (pin "17") (pinfunction "B2_17") (pintype "bidirectional"))
      (node (ref "IC3") (pin "4") (pinfunction "2D_4") (pintype "input"))
      (node (ref "IC4") (pin "4") (pinfunction "2D_4") (pintype "input"))
      (node (ref "IC5") (pin "4") (pinfunction "2D_4") (pintype "input"))
      (node (ref "IC6") (pin "4") (pinfunction "2D_4") (pintype "input"))
      (node (ref "IC7") (pin "4") (pinfunction "2D_4") (pintype "input"))
      (node (ref "IC8") (pin "4") (pinfunction "2D_4") (pintype "input"))
      (node (ref "SV9") (pin "2") (pinfunction "2_2") (pintype "passive"))
    )
    (net (code "223") (name "PIA-A2") (class "Default")
      (node (ref "IC1") (pin "7") (pinfunction "3D_7") (pintype "input"))
      (node (ref "IC11") (pin "6") (pinfunction "3Q_6") (pintype "tri_state"))
      (node (ref "IC12") (pin "6") (pinfunction "3Q_6") (pintype "tri_state"))
      (node (ref "IC13") (pin "6") (pinfunction "3Q_6") (pintype "tri_state"))
      (node (ref "IC14") (pin "6") (pinfunction "3Q_6") (pintype "tri_state"))
      (node (ref "IC15") (pin "6") (pinfunction "3Q_6") (pintype "tri_state"))
      (node (ref "IC16") (pin "6") (pinfunction "3Q_6") (pintype "tri_state"))
      (node (ref "IC2") (pin "7") (pinfunction "3D_7") (pintype "input"))
      (node (ref "IC25") (pin "16") (pinfunction "B3_16") (pintype "bidirectional"))
      (node (ref "IC3") (pin "7") (pinfunction "3D_7") (pintype "input"))
      (node (ref "IC4") (pin "7") (pinfunction "3D_7") (pintype "input"))
      (node (ref "IC5") (pin "7") (pinfunction "3D_7") (pintype "input"))
      (node (ref "IC6") (pin "7") (pinfunction "3D_7") (pintype "input"))
      (node (ref "IC7") (pin "7") (pinfunction "3D_7") (pintype "input"))
      (node (ref "IC8") (pin "7") (pinfunction "3D_7") (pintype "input"))
      (node (ref "SV9") (pin "3") (pinfunction "3_3") (pintype "passive"))
    )
    (net (code "224") (name "PIA-A3") (class "Default")
      (node (ref "IC1") (pin "8") (pinfunction "4D_8") (pintype "input"))
      (node (ref "IC11") (pin "9") (pinfunction "4Q_9") (pintype "tri_state"))
      (node (ref "IC12") (pin "9") (pinfunction "4Q_9") (pintype "tri_state"))
      (node (ref "IC13") (pin "9") (pinfunction "4Q_9") (pintype "tri_state"))
      (node (ref "IC14") (pin "9") (pinfunction "4Q_9") (pintype "tri_state"))
      (node (ref "IC15") (pin "9") (pinfunction "4Q_9") (pintype "tri_state"))
      (node (ref "IC16") (pin "9") (pinfunction "4Q_9") (pintype "tri_state"))
      (node (ref "IC2") (pin "8") (pinfunction "4D_8") (pintype "input"))
      (node (ref "IC25") (pin "15") (pinfunction "B4_15") (pintype "bidirectional"))
      (node (ref "IC3") (pin "8") (pinfunction "4D_8") (pintype "input"))
      (node (ref "IC4") (pin "8") (pinfunction "4D_8") (pintype "input"))
      (node (ref "IC5") (pin "8") (pinfunction "4D_8") (pintype "input"))
      (node (ref "IC6") (pin "8") (pinfunction "4D_8") (pintype "input"))
      (node (ref "IC7") (pin "8") (pinfunction "4D_8") (pintype "input"))
      (node (ref "IC8") (pin "8") (pinfunction "4D_8") (pintype "input"))
      (node (ref "SV9") (pin "4") (pinfunction "4_4") (pintype "passive"))
    )
    (net (code "225") (name "PIA-A4") (class "Default")
      (node (ref "IC1") (pin "13") (pinfunction "5D_13") (pintype "input"))
      (node (ref "IC11") (pin "12") (pinfunction "5Q_12") (pintype "tri_state"))
      (node (ref "IC12") (pin "12") (pinfunction "5Q_12") (pintype "tri_state"))
      (node (ref "IC13") (pin "12") (pinfunction "5Q_12") (pintype "tri_state"))
      (node (ref "IC14") (pin "12") (pinfunction "5Q_12") (pintype "tri_state"))
      (node (ref "IC15") (pin "12") (pinfunction "5Q_12") (pintype "tri_state"))
      (node (ref "IC16") (pin "12") (pinfunction "5Q_12") (pintype "tri_state"))
      (node (ref "IC2") (pin "13") (pinfunction "5D_13") (pintype "input"))
      (node (ref "IC25") (pin "14") (pinfunction "B5_14") (pintype "bidirectional"))
      (node (ref "IC3") (pin "13") (pinfunction "5D_13") (pintype "input"))
      (node (ref "IC4") (pin "13") (pinfunction "5D_13") (pintype "input"))
      (node (ref "IC5") (pin "13") (pinfunction "5D_13") (pintype "input"))
      (node (ref "IC6") (pin "13") (pinfunction "5D_13") (pintype "input"))
      (node (ref "IC7") (pin "13") (pinfunction "5D_13") (pintype "input"))
      (node (ref "IC8") (pin "13") (pinfunction "5D_13") (pintype "input"))
      (node (ref "SV9") (pin "5") (pinfunction "5_5") (pintype "passive"))
    )
    (net (code "226") (name "PIA-A5") (class "Default")
      (node (ref "IC1") (pin "14") (pinfunction "6D_14") (pintype "input"))
      (node (ref "IC11") (pin "15") (pinfunction "6Q_15") (pintype "tri_state"))
      (node (ref "IC12") (pin "15") (pinfunction "6Q_15") (pintype "tri_state"))
      (node (ref "IC13") (pin "15") (pinfunction "6Q_15") (pintype "tri_state"))
      (node (ref "IC14") (pin "15") (pinfunction "6Q_15") (pintype "tri_state"))
      (node (ref "IC15") (pin "15") (pinfunction "6Q_15") (pintype "tri_state"))
      (node (ref "IC16") (pin "15") (pinfunction "6Q_15") (pintype "tri_state"))
      (node (ref "IC2") (pin "14") (pinfunction "6D_14") (pintype "input"))
      (node (ref "IC25") (pin "13") (pinfunction "B6_13") (pintype "bidirectional"))
      (node (ref "IC3") (pin "14") (pinfunction "6D_14") (pintype "input"))
      (node (ref "IC4") (pin "14") (pinfunction "6D_14") (pintype "input"))
      (node (ref "IC5") (pin "14") (pinfunction "6D_14") (pintype "input"))
      (node (ref "IC6") (pin "14") (pinfunction "6D_14") (pintype "input"))
      (node (ref "IC7") (pin "14") (pinfunction "6D_14") (pintype "input"))
      (node (ref "IC8") (pin "14") (pinfunction "6D_14") (pintype "input"))
      (node (ref "SV9") (pin "6") (pinfunction "6_6") (pintype "passive"))
    )
    (net (code "227") (name "PIA-A6") (class "Default")
      (node (ref "IC1") (pin "17") (pinfunction "7D_17") (pintype "input"))
      (node (ref "IC11") (pin "16") (pinfunction "7Q_16") (pintype "tri_state"))
      (node (ref "IC12") (pin "16") (pinfunction "7Q_16") (pintype "tri_state"))
      (node (ref "IC13") (pin "16") (pinfunction "7Q_16") (pintype "tri_state"))
      (node (ref "IC14") (pin "16") (pinfunction "7Q_16") (pintype "tri_state"))
      (node (ref "IC15") (pin "16") (pinfunction "7Q_16") (pintype "tri_state"))
      (node (ref "IC16") (pin "16") (pinfunction "7Q_16") (pintype "tri_state"))
      (node (ref "IC2") (pin "17") (pinfunction "7D_17") (pintype "input"))
      (node (ref "IC25") (pin "12") (pinfunction "B7_12") (pintype "bidirectional"))
      (node (ref "IC3") (pin "17") (pinfunction "7D_17") (pintype "input"))
      (node (ref "IC4") (pin "17") (pinfunction "7D_17") (pintype "input"))
      (node (ref "IC5") (pin "17") (pinfunction "7D_17") (pintype "input"))
      (node (ref "IC6") (pin "17") (pinfunction "7D_17") (pintype "input"))
      (node (ref "IC7") (pin "17") (pinfunction "7D_17") (pintype "input"))
      (node (ref "IC8") (pin "17") (pinfunction "7D_17") (pintype "input"))
      (node (ref "SV9") (pin "7") (pinfunction "7_7") (pintype "passive"))
    )
    (net (code "228") (name "PIA-A7") (class "Default")
      (node (ref "IC1") (pin "18") (pinfunction "8D_18") (pintype "input"))
      (node (ref "IC11") (pin "19") (pinfunction "8Q_19") (pintype "tri_state"))
      (node (ref "IC12") (pin "19") (pinfunction "8Q_19") (pintype "tri_state"))
      (node (ref "IC13") (pin "19") (pinfunction "8Q_19") (pintype "tri_state"))
      (node (ref "IC14") (pin "19") (pinfunction "8Q_19") (pintype "tri_state"))
      (node (ref "IC15") (pin "19") (pinfunction "8Q_19") (pintype "tri_state"))
      (node (ref "IC16") (pin "19") (pinfunction "8Q_19") (pintype "tri_state"))
      (node (ref "IC2") (pin "18") (pinfunction "8D_18") (pintype "input"))
      (node (ref "IC25") (pin "11") (pinfunction "B8_11") (pintype "bidirectional"))
      (node (ref "IC3") (pin "18") (pinfunction "8D_18") (pintype "input"))
      (node (ref "IC4") (pin "18") (pinfunction "8D_18") (pintype "input"))
      (node (ref "IC5") (pin "18") (pinfunction "8D_18") (pintype "input"))
      (node (ref "IC6") (pin "18") (pinfunction "8D_18") (pintype "input"))
      (node (ref "IC7") (pin "18") (pinfunction "8D_18") (pintype "input"))
      (node (ref "IC8") (pin "18") (pinfunction "8D_18") (pintype "input"))
      (node (ref "SV9") (pin "8") (pinfunction "8_8") (pintype "passive"))
    )
    (net (code "229") (name "PIA-B0") (class "Default")
      (node (ref "IC10") (pin "23") (pinfunction "A_23") (pintype "input"))
      (node (ref "IC26") (pin "18") (pinfunction "B1_18") (pintype "bidirectional"))
      (node (ref "IC9") (pin "23") (pinfunction "A_23") (pintype "input"))
      (node (ref "SV9") (pin "13") (pinfunction "13_13") (pintype "passive"))
    )
    (net (code "230") (name "PIA-B1") (class "Default")
      (node (ref "IC10") (pin "22") (pinfunction "B_22") (pintype "input"))
      (node (ref "IC26") (pin "17") (pinfunction "B2_17") (pintype "bidirectional"))
      (node (ref "IC9") (pin "22") (pinfunction "B_22") (pintype "input"))
      (node (ref "SV9") (pin "14") (pinfunction "14_14") (pintype "passive"))
    )
    (net (code "231") (name "PIA-B2") (class "Default")
      (node (ref "IC10") (pin "21") (pinfunction "C_21") (pintype "input"))
      (node (ref "IC26") (pin "16") (pinfunction "B3_16") (pintype "bidirectional"))
      (node (ref "IC9") (pin "21") (pinfunction "C_21") (pintype "input"))
      (node (ref "SV9") (pin "15") (pinfunction "15_15") (pintype "passive"))
    )
    (net (code "232") (name "PIA-B3") (class "Default")
      (node (ref "IC10") (pin "20") (pinfunction "D_20") (pintype "input"))
      (node (ref "IC26") (pin "15") (pinfunction "B4_15") (pintype "bidirectional"))
      (node (ref "IC9") (pin "20") (pinfunction "D_20") (pintype "input"))
      (node (ref "SV9") (pin "16") (pinfunction "16_16") (pintype "passive"))
    )
    (net (code "233") (name "PIA-B4") (class "Default")
      (node (ref "IC26") (pin "14") (pinfunction "B5_14") (pintype "bidirectional"))
      (node (ref "IC9") (pin "18") (pinfunction "G1_18") (pintype "input"))
      (node (ref "SV9") (pin "17") (pinfunction "17_17") (pintype "passive"))
    )
    (net (code "234") (name "PIA-B5") (class "Default")
      (node (ref "IC10") (pin "18") (pinfunction "G1_18") (pintype "input"))
      (node (ref "IC26") (pin "13") (pinfunction "B6_13") (pintype "bidirectional"))
      (node (ref "SV9") (pin "18") (pinfunction "18_18") (pintype "passive"))
    )
    (net (code "235") (name "PIA-B6") (class "Default")
      (node (ref "IC26") (pin "12") (pinfunction "B7_12") (pintype "bidirectional"))
      (node (ref "SV9") (pin "19") (pinfunction "19_19") (pintype "passive"))
    )
    (net (code "236") (name "PIA-B7") (class "Default")
      (node (ref "IC26") (pin "11") (pinfunction "B8_11") (pintype "bidirectional"))
      (node (ref "SV9") (pin "20") (pinfunction "20_20") (pintype "passive"))
    )
    (net (code "237") (name "RX") (class "Default")
      (node (ref "IC20") (pin "12") (pinfunction "R1OUT_12") (pintype "output"))
      (node (ref "IC21") (pin "2") (pinfunction "RXDATA_2") (pintype "input"))
    )
    (net (code "238") (name "RXD") (class "Default")
      (node (ref "IC20") (pin "13") (pinfunction "R1IN_13") (pintype "input"))
      (node (ref "X1") (pin "2") (pinfunction "2_2") (pintype "passive"))
    )
    (net (code "239") (name "R{slash}~{W}") (class "Default")
      (node (ref "IC17") (pin "34") (pinfunction "R/~{W}_34") (pintype "output"))
      (node (ref "IC21") (pin "13") (pinfunction "R/~{W}_13") (pintype "input"))
      (node (ref "IC22") (pin "27") (pinfunction "~{PGM}_27") (pintype "input"))
      (node (ref "IC24") (pin "21") (pinfunction "R/~{W}_21") (pintype "input"))
    )
    (net (code "240") (name "TX") (class "Default")
      (node (ref "IC20") (pin "11") (pinfunction "T1IN_11") (pintype "input"))
      (node (ref "IC21") (pin "6") (pinfunction "TXDATA_6") (pintype "output"))
    )
    (net (code "241") (name "TXD") (class "Default")
      (node (ref "IC20") (pin "14") (pinfunction "T1OUT_14") (pintype "output"))
      (node (ref "X1") (pin "3") (pinfunction "3_3") (pintype "passive"))
    )
    (net (code "242") (name "VCC") (class "Default")
      (node (ref "BYP1") (pin "1") (pinfunction "1_1") (pintype "passive"))
      (node (ref "BYP10") (pin "1") (pinfunction "1_1") (pintype "passive"))
      (node (ref "BYP11") (pin "1") (pinfunction "1_1") (pintype "passive"))
      (node (ref "BYP12") (pin "1") (pinfunction "1_1") (pintype "passive"))
      (node (ref "BYP13") (pin "1") (pinfunction "1_1") (pintype "passive"))
      (node (ref "BYP14") (pin "1") (pinfunction "1_1") (pintype "passive"))
      (node (ref "BYP15") (pin "1") (pinfunction "1_1") (pintype "passive"))
      (node (ref "BYP16") (pin "1") (pinfunction "1_1") (pintype "passive"))
      (node (ref "BYP17") (pin "1") (pinfunction "1_1") (pintype "passive"))
      (node (ref "BYP18") (pin "1") (pinfunction "1_1") (pintype "passive"))
      (node (ref "BYP19") (pin "1") (pinfunction "1_1") (pintype "passive"))
      (node (ref "BYP2") (pin "1") (pinfunction "1_1") (pintype "passive"))
      (node (ref "BYP20") (pin "1") (pinfunction "1_1") (pintype "passive"))
      (node (ref "BYP21") (pin "1") (pinfunction "1_1") (pintype "passive"))
      (node (ref "BYP22") (pin "1") (pinfunction "1_1") (pintype "passive"))
      (node (ref "BYP23") (pin "1") (pinfunction "1_1") (pintype "passive"))
      (node (ref "BYP24") (pin "1") (pinfunction "1_1") (pintype "passive"))
      (node (ref "BYP25") (pin "1") (pinfunction "1_1") (pintype "passive"))
      (node (ref "BYP26") (pin "1") (pinfunction "1_1") (pintype "passive"))
      (node (ref "BYP27") (pin "1") (pinfunction "1_1") (pintype "passive"))
      (node (ref "BYP28") (pin "1") (pinfunction "1_1") (pintype "passive"))
      (node (ref "BYP29") (pin "1") (pinfunction "1_1") (pintype "passive"))
      (node (ref "BYP3") (pin "1") (pinfunction "1_1") (pintype "passive"))
      (node (ref "BYP4") (pin "1") (pinfunction "1_1") (pintype "passive"))
      (node (ref "BYP5") (pin "1") (pinfunction "1_1") (pintype "passive"))
      (node (ref "BYP6") (pin "1") (pinfunction "1_1") (pintype "passive"))
      (node (ref "BYP7") (pin "1") (pinfunction "1_1") (pintype "passive"))
      (node (ref "BYP8") (pin "1") (pinfunction "1_1") (pintype "passive"))
      (node (ref "BYP9") (pin "1") (pinfunction "1_1") (pintype "passive"))
      (node (ref "C10") (pin "1") (pinfunction "1_1") (pintype "passive"))
      (node (ref "IC11") (pin "11") (pinfunction "ENC_11") (pintype "input"))
      (node (ref "IC12") (pin "11") (pinfunction "ENC_11") (pintype "input"))
      (node (ref "IC13") (pin "11") (pinfunction "ENC_11") (pintype "input"))
      (node (ref "IC14") (pin "11") (pinfunction "ENC_11") (pintype "input"))
      (node (ref "IC15") (pin "11") (pinfunction "ENC_11") (pintype "input"))
      (node (ref "IC16") (pin "11") (pinfunction "ENC_11") (pintype "input"))
      (node (ref "IC17") (pin "35") (pinfunction "VCCSTB_35") (pintype "input"))
      (node (ref "IC17") (pin "36") (pinfunction "RE_36") (pintype "input"))
      (node (ref "IC17") (pin "8") (pinfunction "VCC_8") (pintype "power_in"))
      (node (ref "IC21") (pin "10") (pinfunction "CS1_10") (pintype "input"))
      (node (ref "IC21") (pin "12") (pinfunction "VCC_12") (pintype "power_in"))
      (node (ref "IC21") (pin "8") (pinfunction "CS0_8") (pintype "input"))
      (node (ref "IC22") (pin "1") (pinfunction "VPP_1") (pintype "input"))
      (node (ref "IC23") (pin "1") (pinfunction "VPP_1") (pintype "input"))
      (node (ref "IC23") (pin "27") (pinfunction "~{PGM}_27") (pintype "input"))
      (node (ref "IC24") (pin "20") (pinfunction "VCC_20") (pintype "power_in"))
      (node (ref "IC24") (pin "22") (pinfunction "CS0_22") (pintype "input"))
      (node (ref "IC24") (pin "24") (pinfunction "CS1_24") (pintype "input"))
      (node (ref "IC27") (pin "10") (pinfunction "R_10") (pintype "input"))
      (node (ref "IC27") (pin "14") (pinfunction "V+_14") (pintype "power_in"))
      (node (ref "IC27") (pin "4") (pinfunction "R_4") (pintype "input"))
      (node (ref "IC28") (pin "6") (pinfunction "G1_6") (pintype "input"))
      (node (ref "IC29") (pin "1") (pinfunction "VPP_1") (pintype "input"))
      (node (ref "IC29") (pin "27") (pinfunction "~{PGM}_27") (pintype "input"))
      (node (ref "JP2") (pin "2") (pinfunction "2_2") (pintype "passive"))
      (node (ref "R1") (pin "2") (pinfunction "2_2") (pintype "passive"))
      (node (ref "R12") (pin "2") (pinfunction "2_2") (pintype "passive"))
      (node (ref "R14") (pin "2") (pinfunction "2_2") (pintype "passive"))
      (node (ref "R2") (pin "2") (pinfunction "2_2") (pintype "passive"))
      (node (ref "R3") (pin "2") (pinfunction "2_2") (pintype "passive"))
      (node (ref "R5") (pin "2") (pinfunction "2_2") (pintype "passive"))
      (node (ref "R6") (pin "2") (pinfunction "2_2") (pintype "passive"))
      (node (ref "R7") (pin "2") (pinfunction "2_2") (pintype "passive"))
      (node (ref "R8") (pin "2") (pinfunction "2_2") (pintype "passive"))
      (node (ref "R9") (pin "2") (pinfunction "2_2") (pintype "passive"))
      (node (ref "SV9") (pin "11") (pinfunction "11_11") (pintype "passive"))
      (node (ref "SV9") (pin "12") (pinfunction "12_12") (pintype "passive"))
    )
    (net (code "243") (name "VMA") (class "Default")
      (node (ref "IC17") (pin "5") (pinfunction "VMA_5") (pintype "output"))
      (node (ref "IC18") (pin "9") (pinfunction "I0_9") (pintype "input"))
    )
    (net (code "244") (name "unconnected-(IC17A-BA-Pad7)") (class "Default")
      (node (ref "IC17") (pin "7") (pinfunction "BA_7") (pintype "output"))
    )
    (net (code "245") (name "unconnected-(IC19A-Y0-Pad15)") (class "Default")
      (node (ref "IC19") (pin "15") (pinfunction "Y0_15") (pintype "output"))
    )
    (net (code "246") (name "unconnected-(IC19A-Y1-Pad14)") (class "Default")
      (node (ref "IC19") (pin "14") (pinfunction "Y1_14") (pintype "output"))
    )
    (net (code "247") (name "unconnected-(IC19A-Y2-Pad13)") (class "Default")
      (node (ref "IC19") (pin "13") (pinfunction "Y2_13") (pintype "output"))
    )
    (net (code "248") (name "unconnected-(IC19A-Y3-Pad12)") (class "Default")
      (node (ref "IC19") (pin "12") (pinfunction "Y3_12") (pintype "output"))
    )
    (net (code "249") (name "unconnected-(IC19A-Y4-Pad11)") (class "Default")
      (node (ref "IC19") (pin "11") (pinfunction "Y4_11") (pintype "output"))
    )
    (net (code "250") (name "unconnected-(IC19A-Y5-Pad10)") (class "Default")
      (node (ref "IC19") (pin "10") (pinfunction "Y5_10") (pintype "output"))
    )
    (net (code "251") (name "unconnected-(IC20A-R2OUT-Pad9)") (class "Default")
      (node (ref "IC20") (pin "9") (pinfunction "R2OUT_9") (pintype "output"))
    )
    (net (code "252") (name "unconnected-(IC28A-Y1-Pad14)") (class "Default")
      (node (ref "IC28") (pin "14") (pinfunction "Y1_14") (pintype "output"))
    )
    (net (code "253") (name "unconnected-(IC28A-Y2-Pad13)") (class "Default")
      (node (ref "IC28") (pin "13") (pinfunction "Y2_13") (pintype "output"))
    )
    (net (code "254") (name "unconnected-(IC28A-Y3-Pad12)") (class "Default")
      (node (ref "IC28") (pin "12") (pinfunction "Y3_12") (pintype "output"))
    )
    (net (code "255") (name "unconnected-(IC28A-Y4-Pad11)") (class "Default")
      (node (ref "IC28") (pin "11") (pinfunction "Y4_11") (pintype "output"))
    )
    (net (code "256") (name "unconnected-(R11-PadS)") (class "Default")
      (node (ref "R11") (pin "S") (pinfunction "S_S") (pintype "passive"))
    )
    (net (code "257") (name "unconnected-(X1-Pad1)") (class "Default")
      (node (ref "X1") (pin "1") (pinfunction "1_1") (pintype "passive"))
    )
    (net (code "258") (name "unconnected-(X1-Pad9)") (class "Default")
      (node (ref "X1") (pin "9") (pinfunction "9_9") (pintype "passive"))
    )
    (net (code "259") (name "~{AB}") (class "Default")
      (node (ref "IC22") (pin "20") (pinfunction "~{CE}_20") (pintype "input"))
      (node (ref "IC22") (pin "22") (pinfunction "~{OE}_22") (pintype "input"))
      (node (ref "IC28") (pin "10") (pinfunction "Y5_10") (pintype "output"))
    )
    (net (code "260") (name "~{CD}") (class "Default")
      (node (ref "IC28") (pin "9") (pinfunction "Y6_9") (pintype "output"))
      (node (ref "IC29") (pin "20") (pinfunction "~{CE}_20") (pintype "input"))
      (node (ref "IC29") (pin "22") (pinfunction "~{OE}_22") (pintype "input"))
    )
    (net (code "261") (name "~{EF}") (class "Default")
      (node (ref "IC23") (pin "20") (pinfunction "~{CE}_20") (pintype "input"))
      (node (ref "IC23") (pin "22") (pinfunction "~{OE}_22") (pintype "input"))
      (node (ref "IC28") (pin "7") (pinfunction "Y7_7") (pintype "output"))
    )
    (net (code "262") (name "~{HLT}") (class "Default")
      (node (ref "IC17") (pin "2") (pinfunction "HALT_2") (pintype "input"))
      (node (ref "R5") (pin "1") (pinfunction "1_1") (pintype "passive"))
    )
    (net (code "263") (name "~{IO-E}") (class "Default")
      (node (ref "IC19") (pin "9") (pinfunction "Y6_9") (pintype "output"))
      (node (ref "IC24") (pin "23") (pinfunction "CS2_23") (pintype "input"))
    )
    (net (code "264") (name "~{IO-F}") (class "Default")
      (node (ref "IC19") (pin "7") (pinfunction "Y7_7") (pintype "output"))
      (node (ref "IC21") (pin "9") (pinfunction "CS2_9") (pintype "input"))
    )
    (net (code "265") (name "~{IRQ}") (class "Default")
      (node (ref "IC17") (pin "4") (pinfunction "IRQ_4") (pintype "input"))
      (node (ref "IC24") (pin "37") (pinfunction "IRQB_37") (pintype "open_collector"))
      (node (ref "IC24") (pin "38") (pinfunction "IRQA_38") (pintype "open_collector"))
      (node (ref "R7") (pin "1") (pinfunction "1_1") (pintype "passive"))
    )
    (net (code "266") (name "~{NMI}") (class "Default")
      (node (ref "IC17") (pin "6") (pinfunction "NMI_6") (pintype "input"))
      (node (ref "IC21") (pin "7") (pinfunction "IRQ_7") (pintype "output"))
      (node (ref "R6") (pin "1") (pinfunction "1_1") (pintype "passive"))
    )
    (net (code "267") (name "~{RST}") (class "Default")
      (node (ref "IC17") (pin "40") (pinfunction "RESET_40") (pintype "input"))
      (node (ref "IC18") (pin "6") (pinfunction "O_6") (pintype "output"))
      (node (ref "IC24") (pin "34") (pinfunction "RESET_34") (pintype "input"))
    )
  )
)
